# Ruri-Passport-RevA.net
KiCad netlist of a schematic drawn in EasyEDA Pro
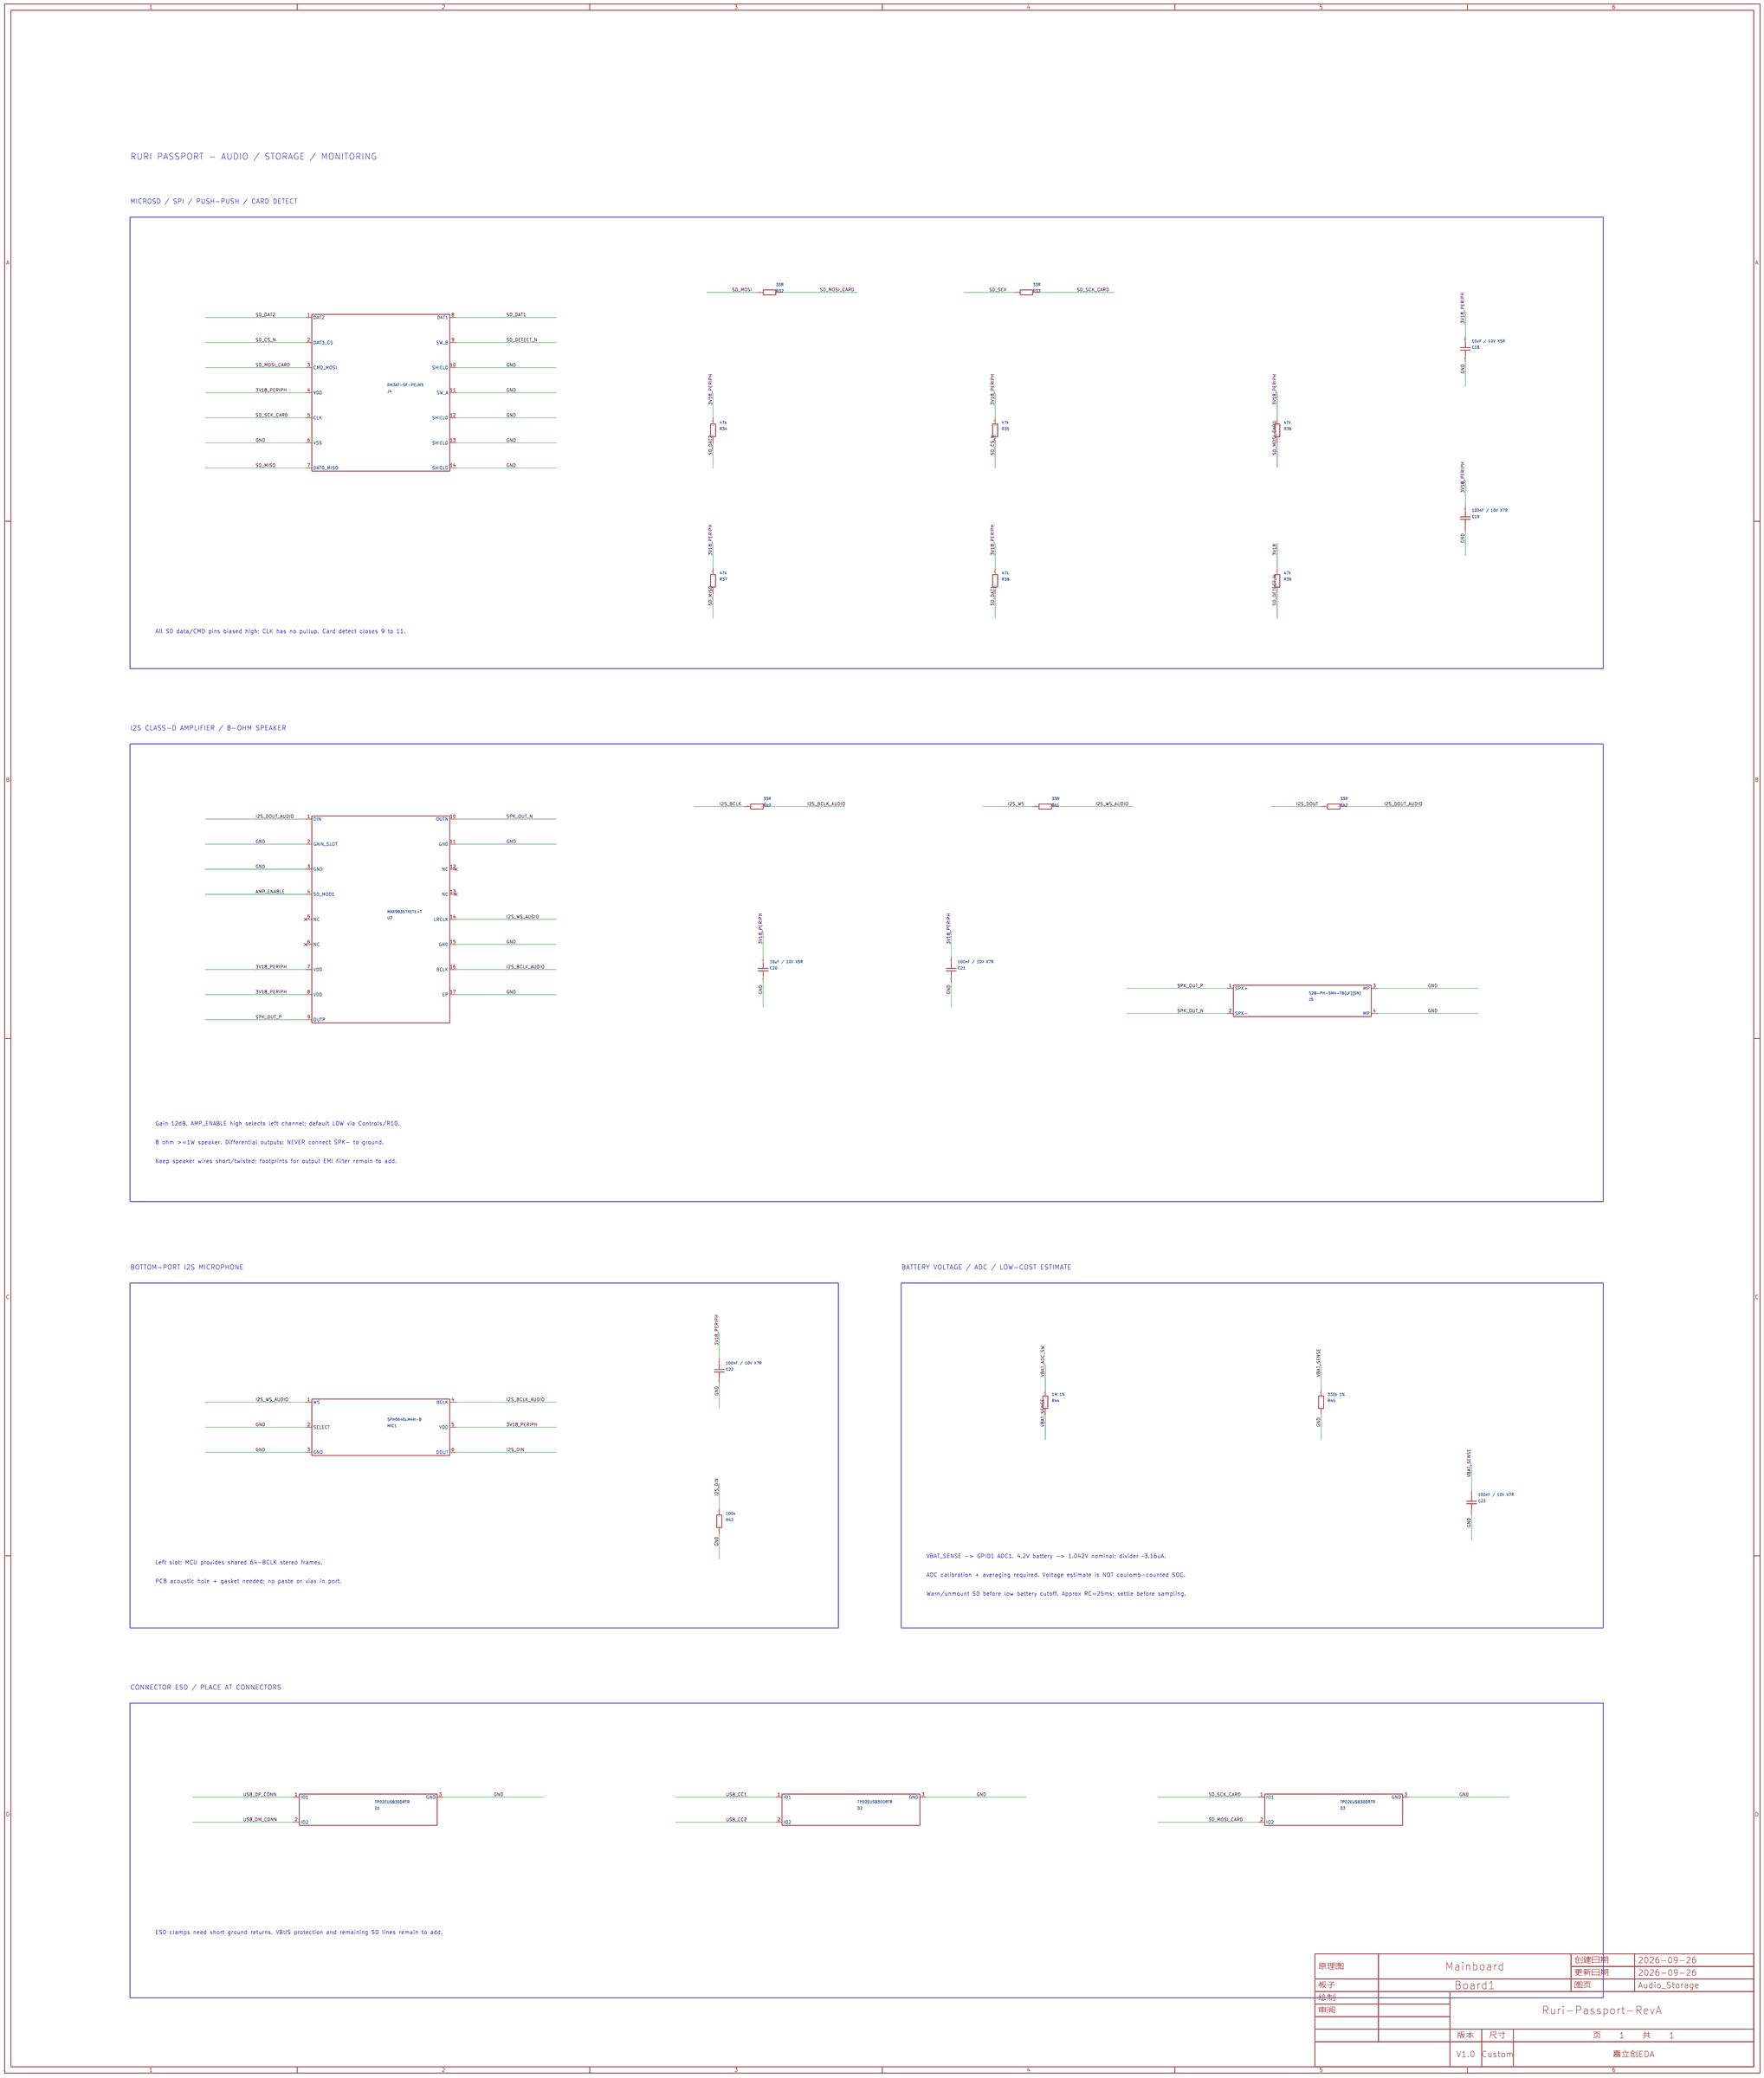
[diagram p0: Audio_Storage]
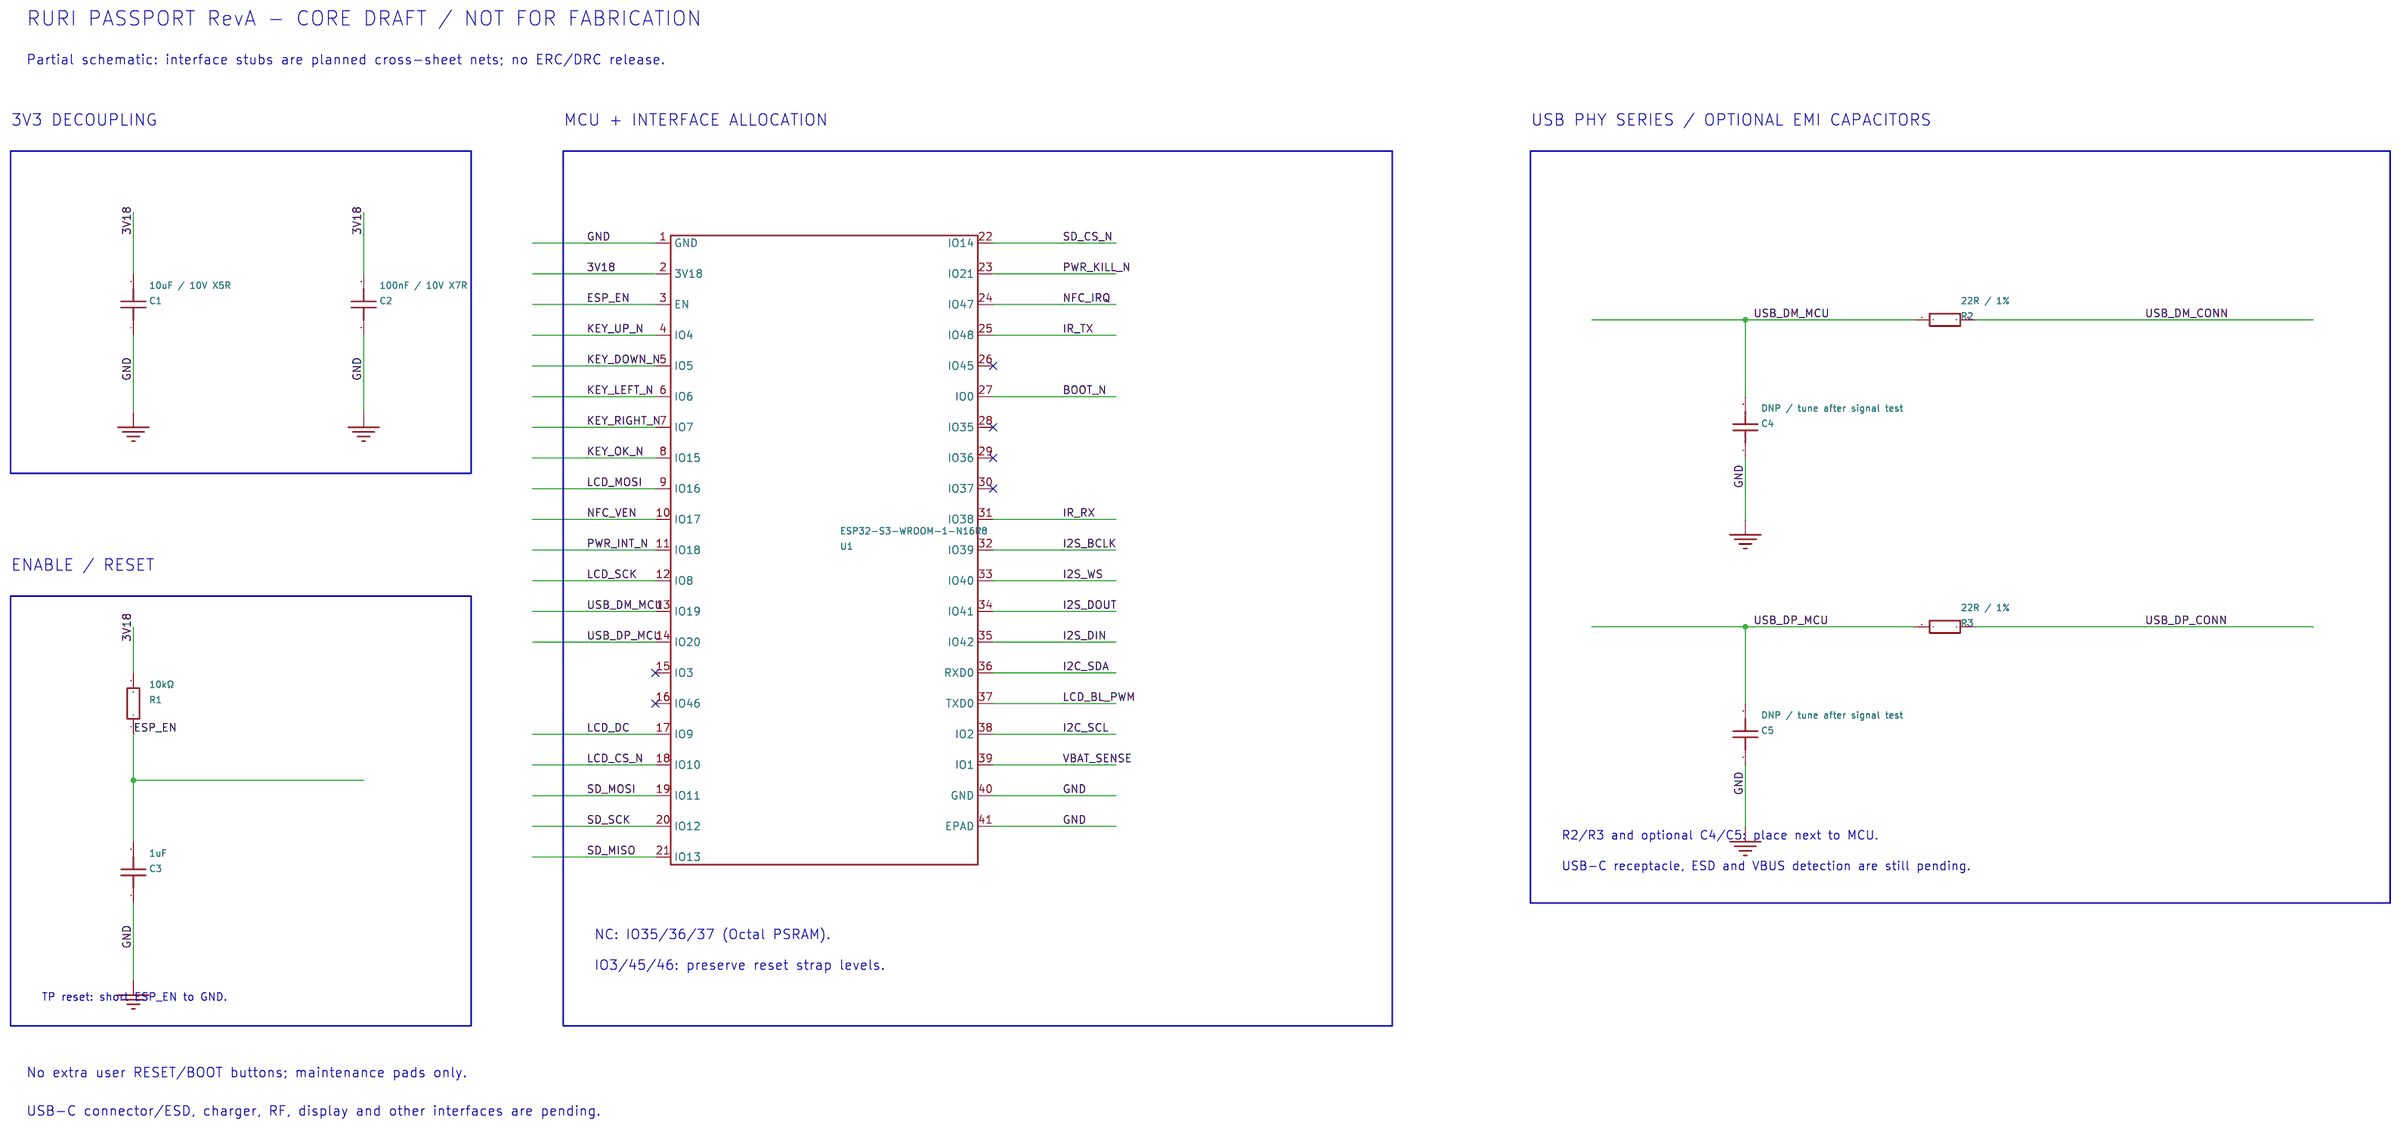
[diagram p1: Core]
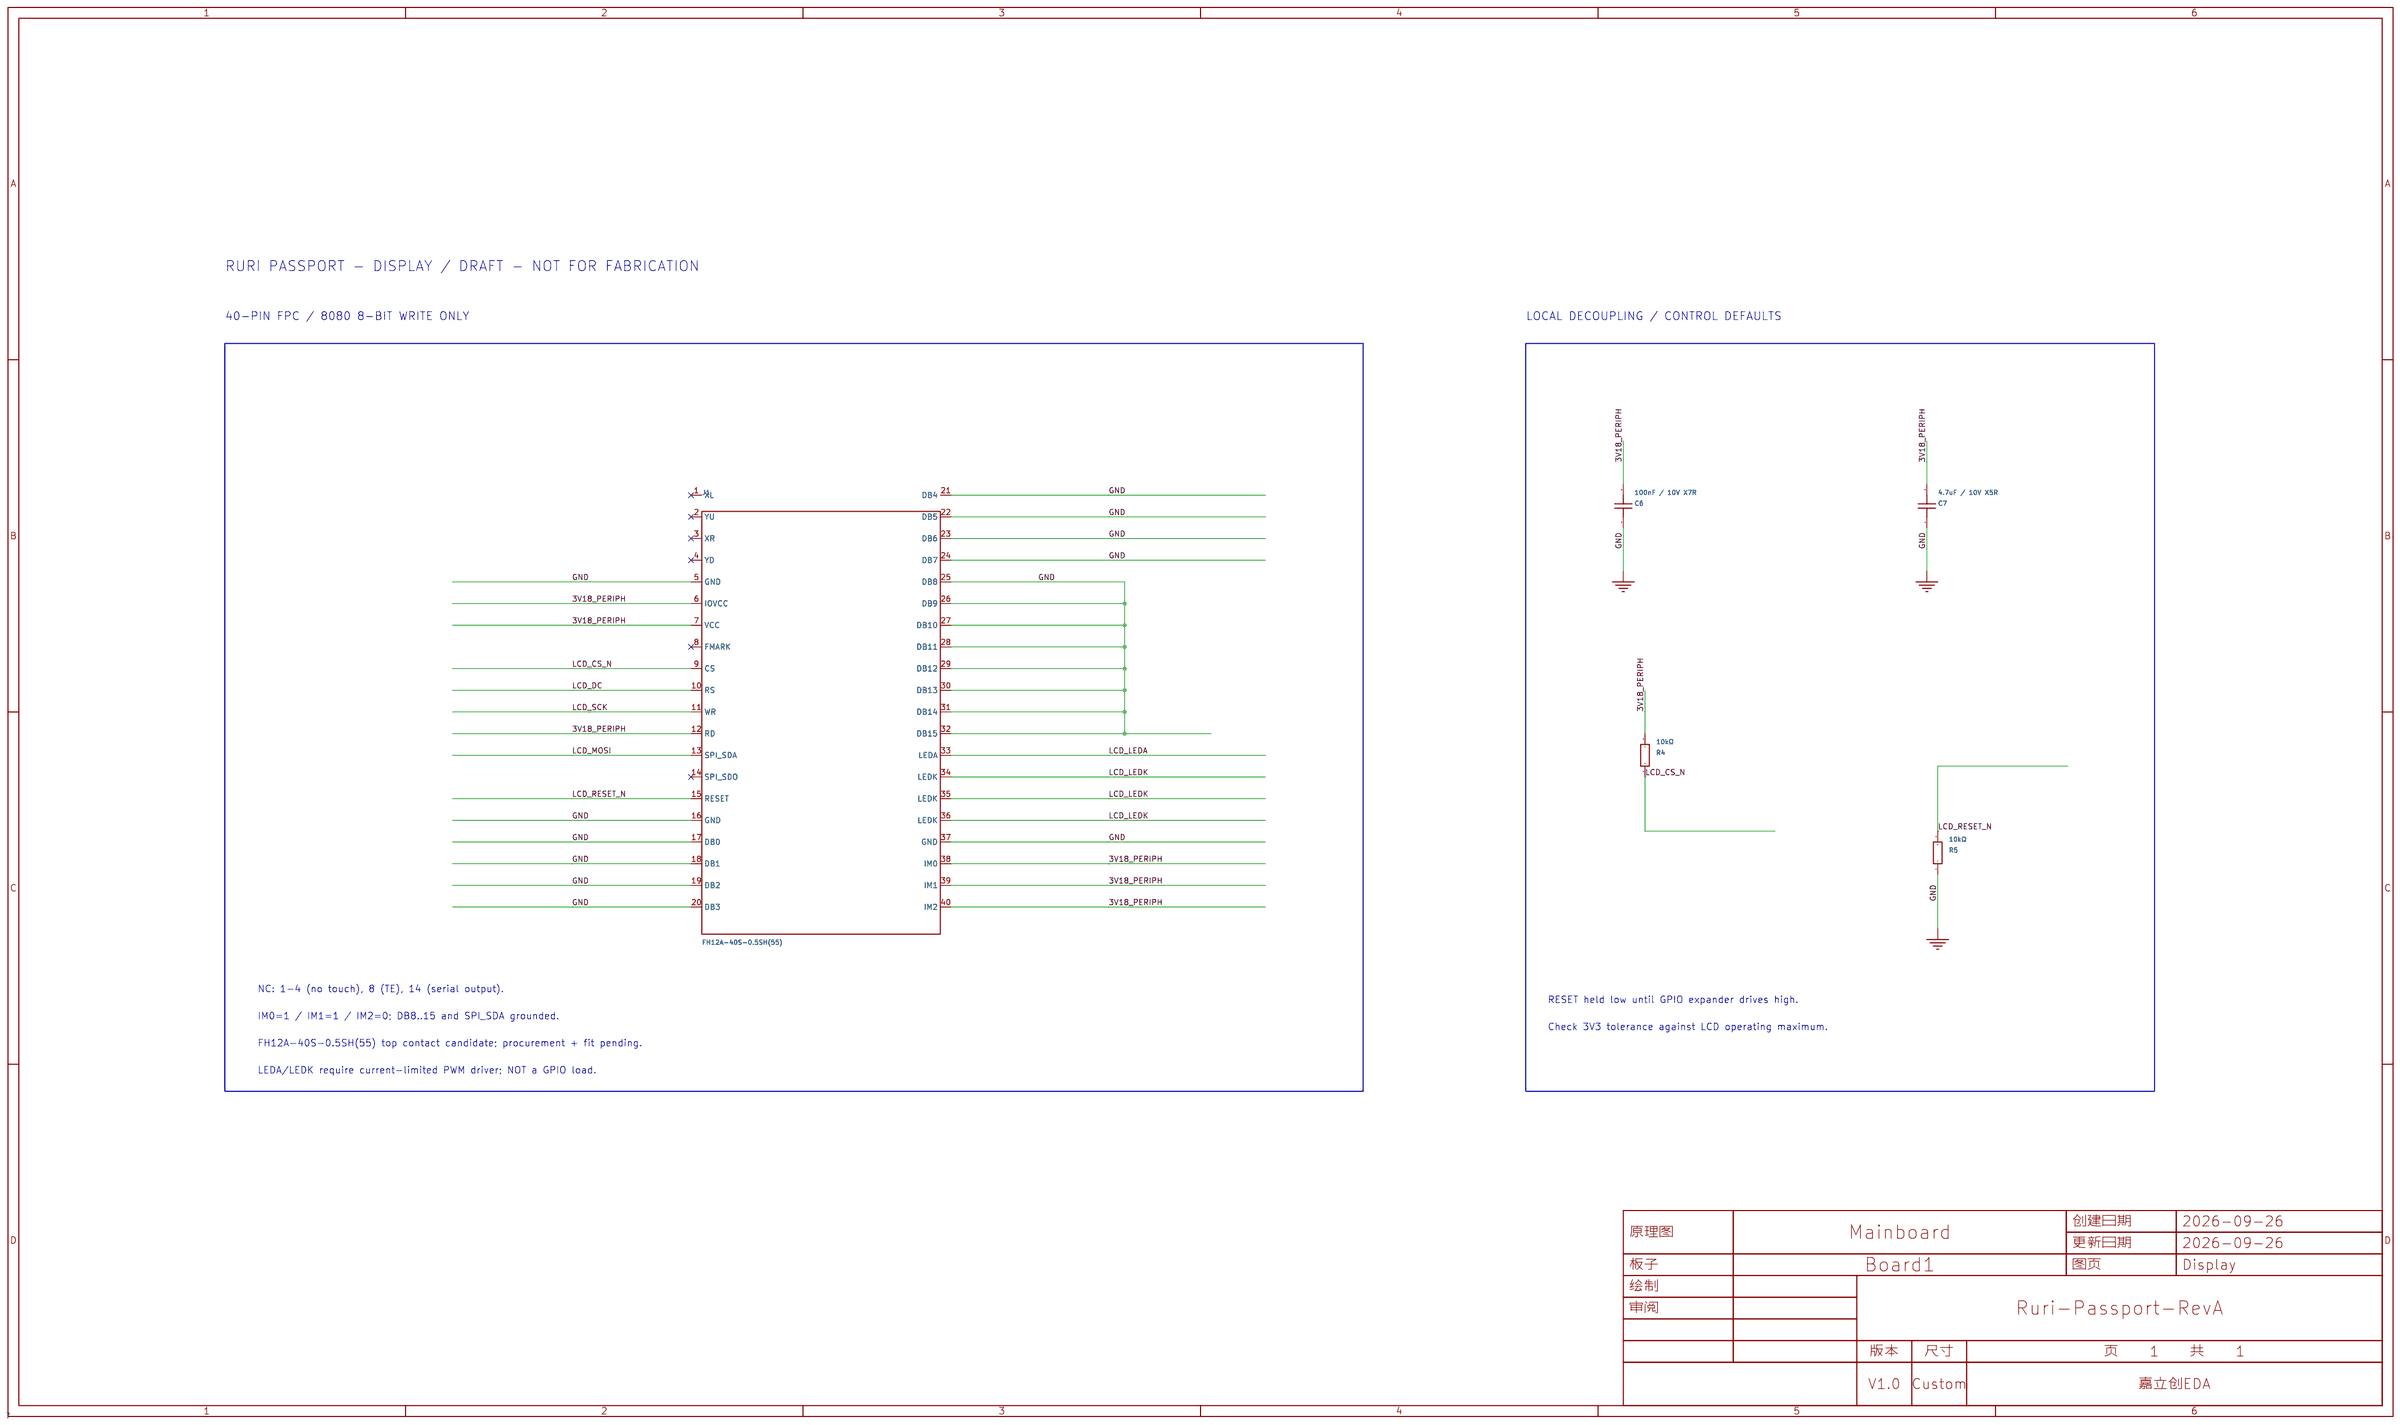
[diagram p2: Display]
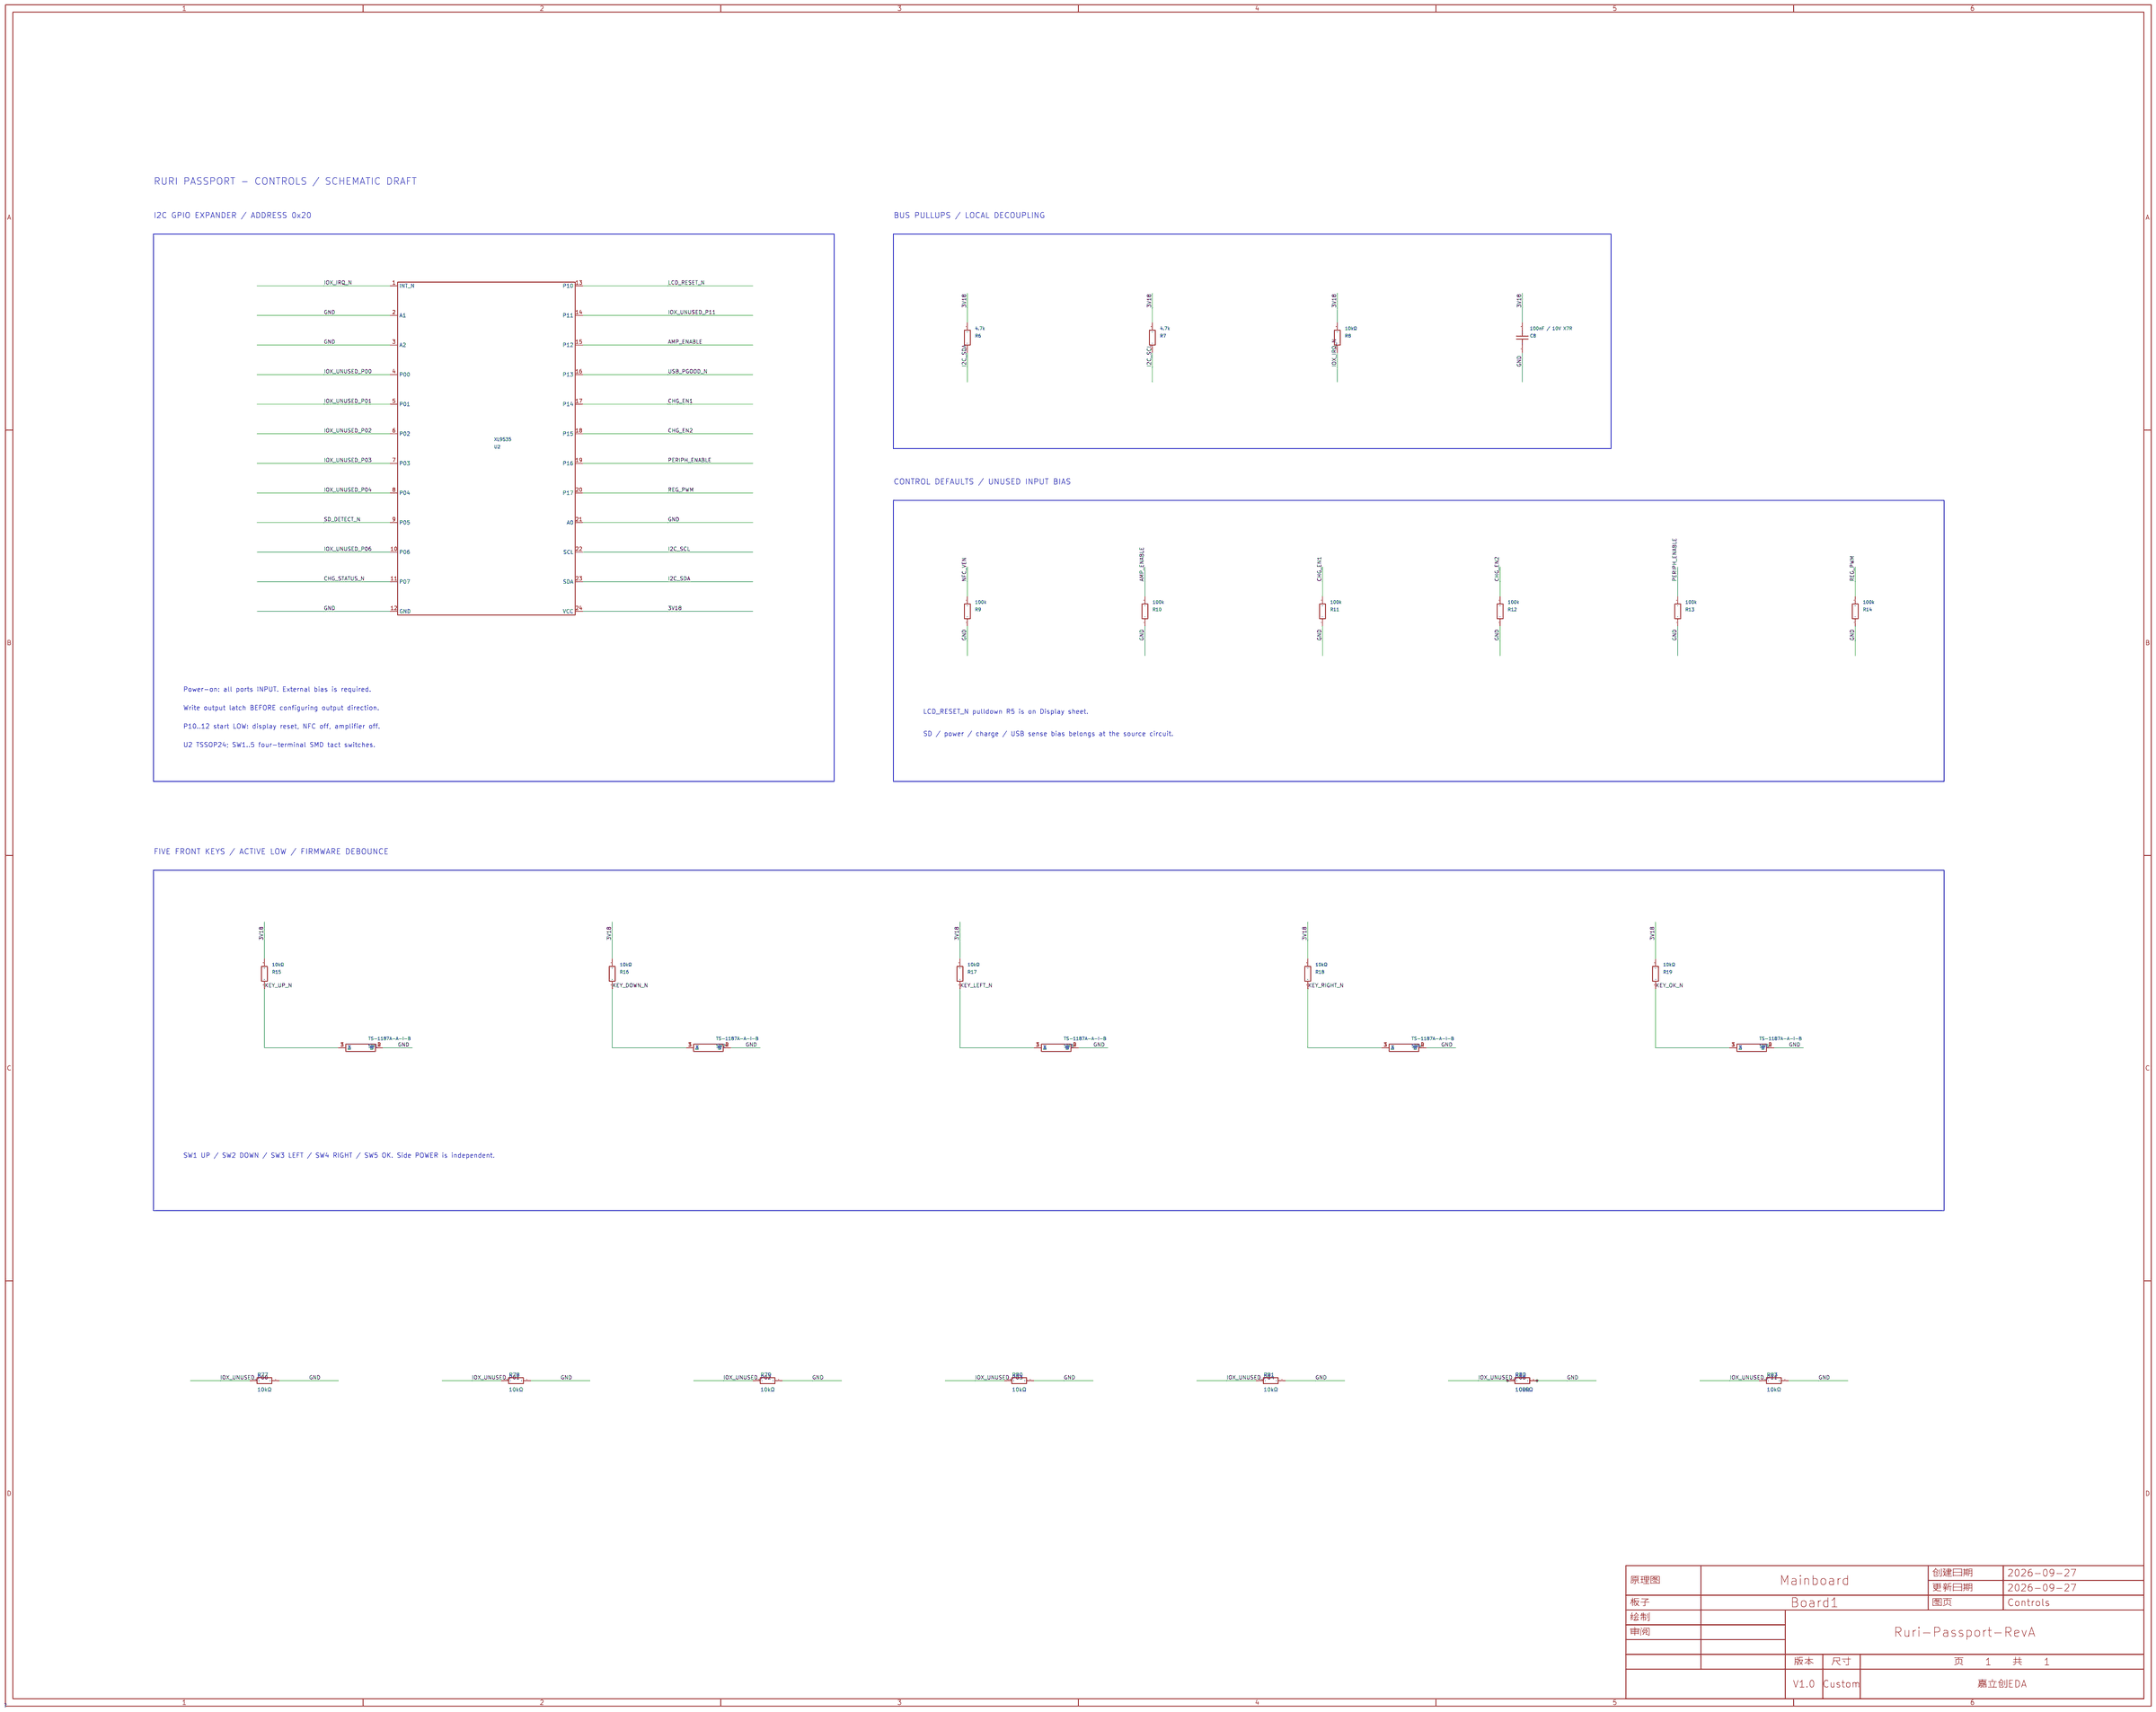
[diagram p3: Controls]
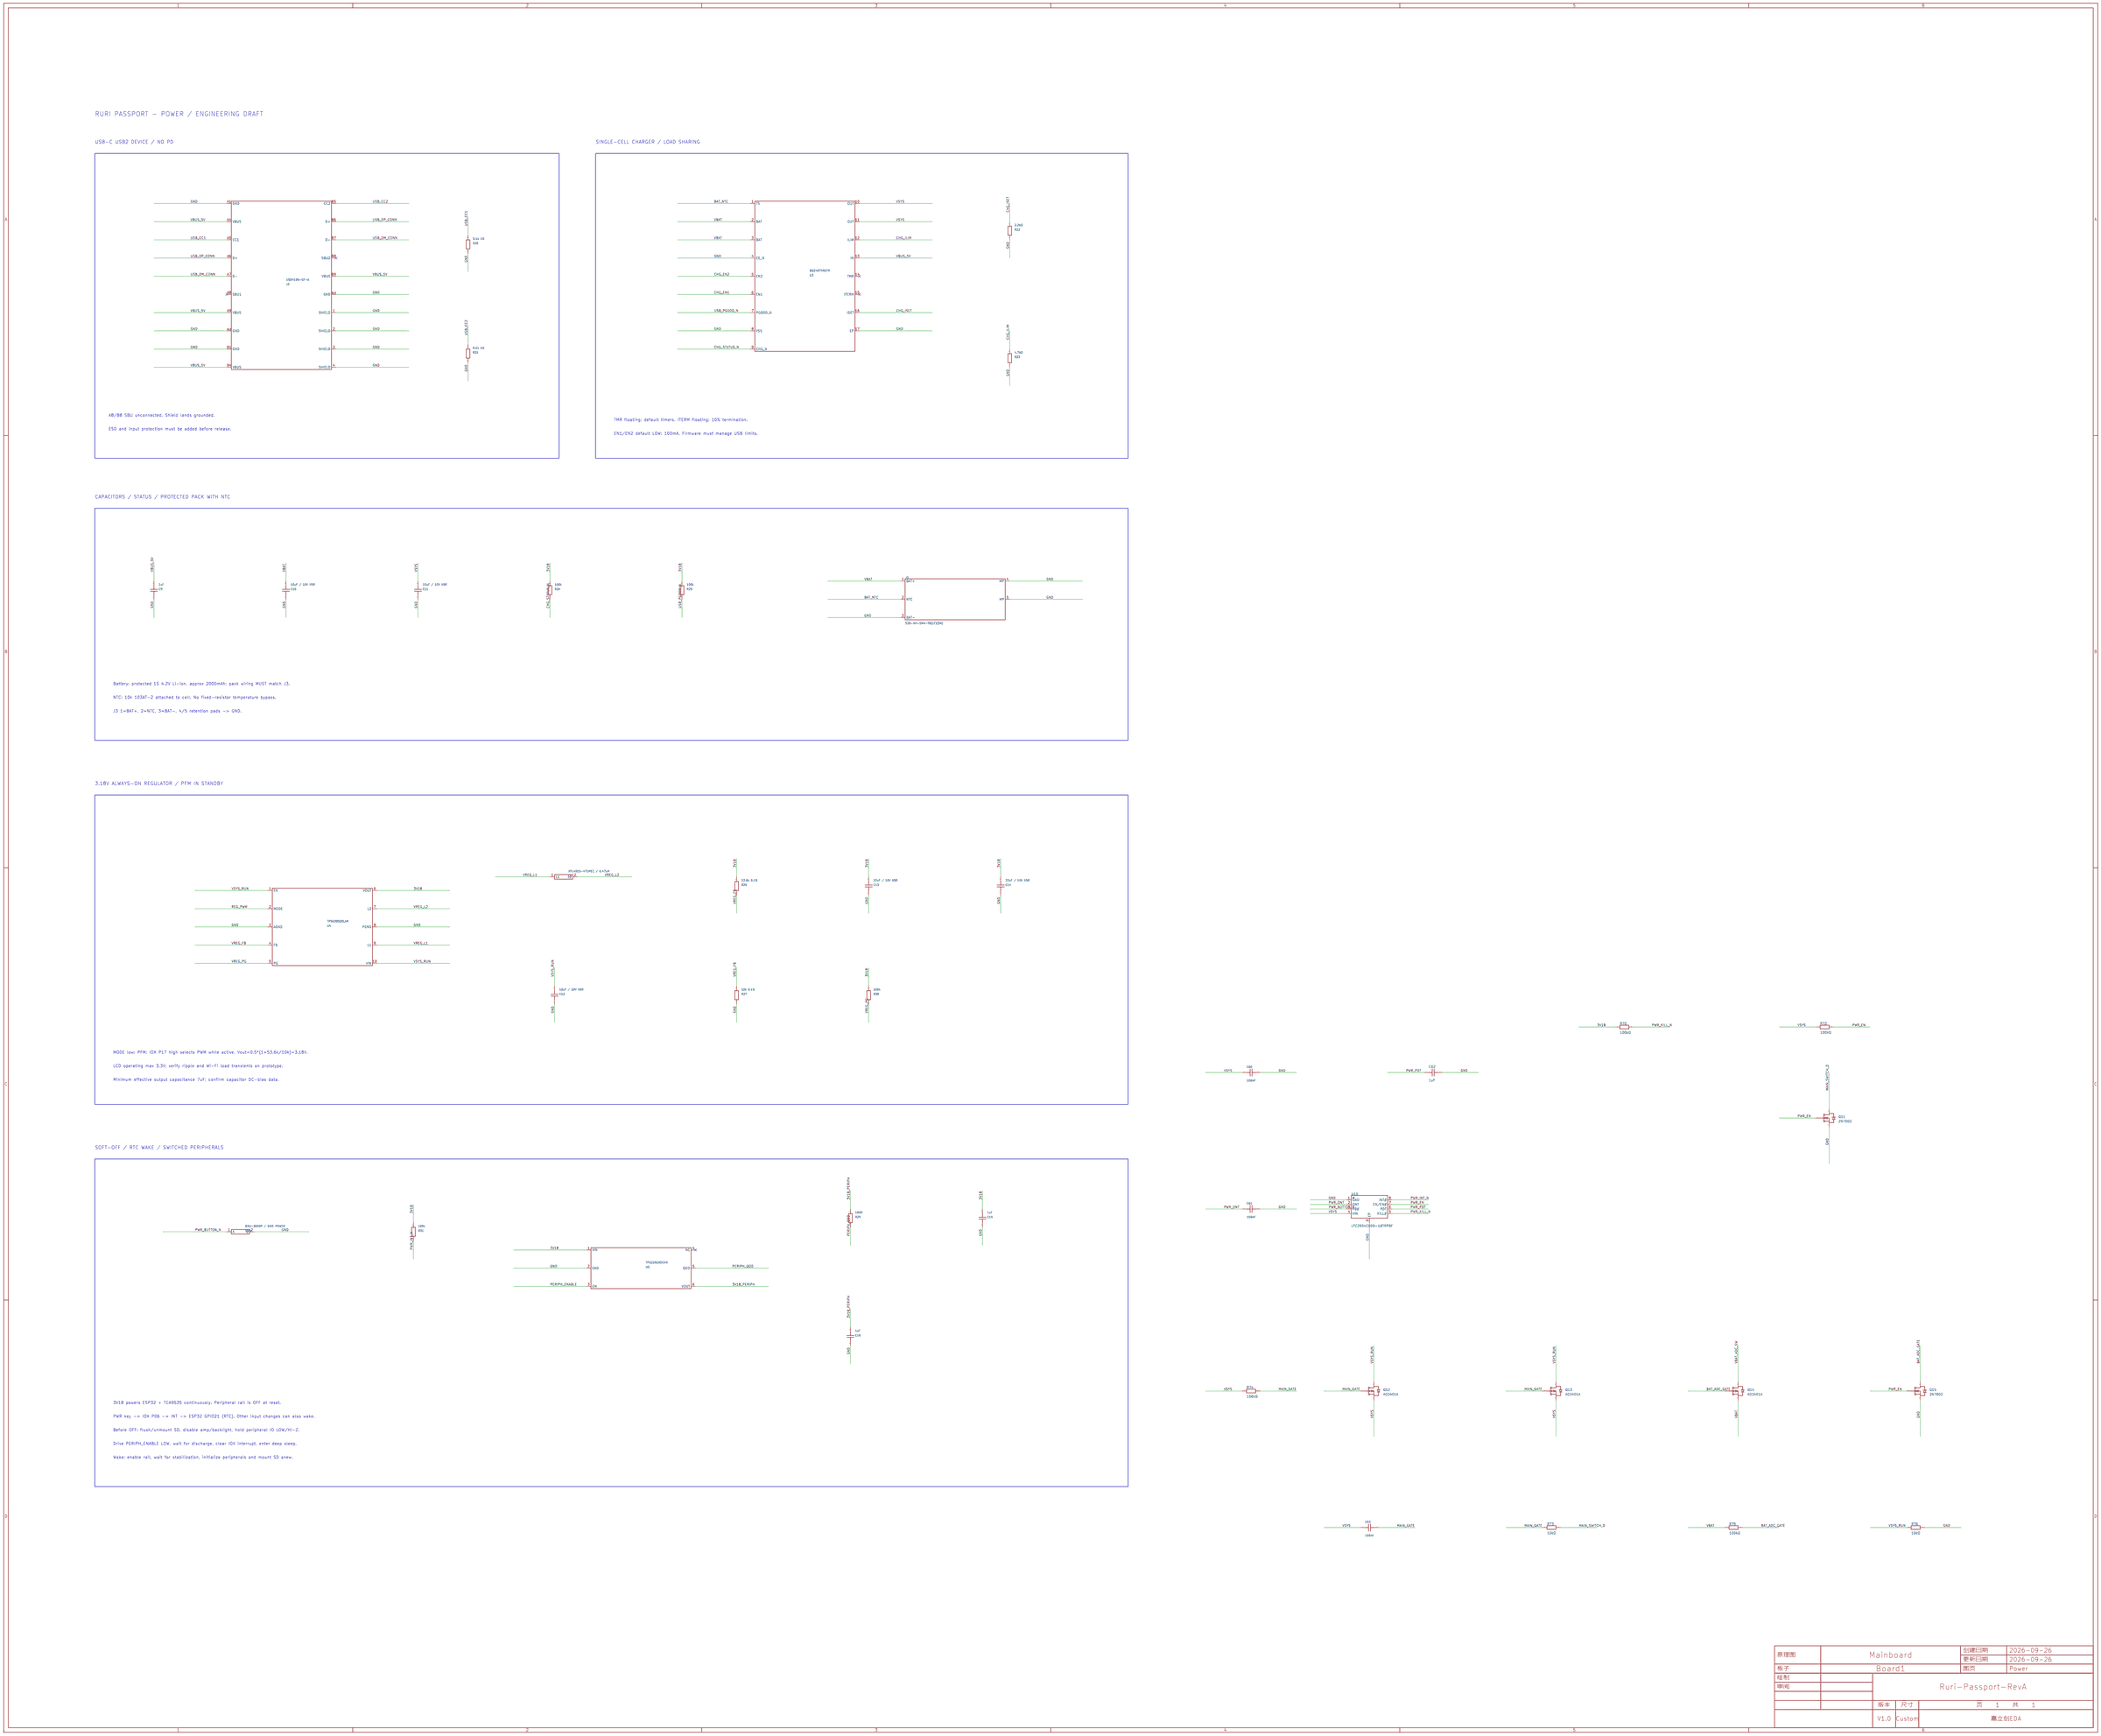
[diagram p4: Power]
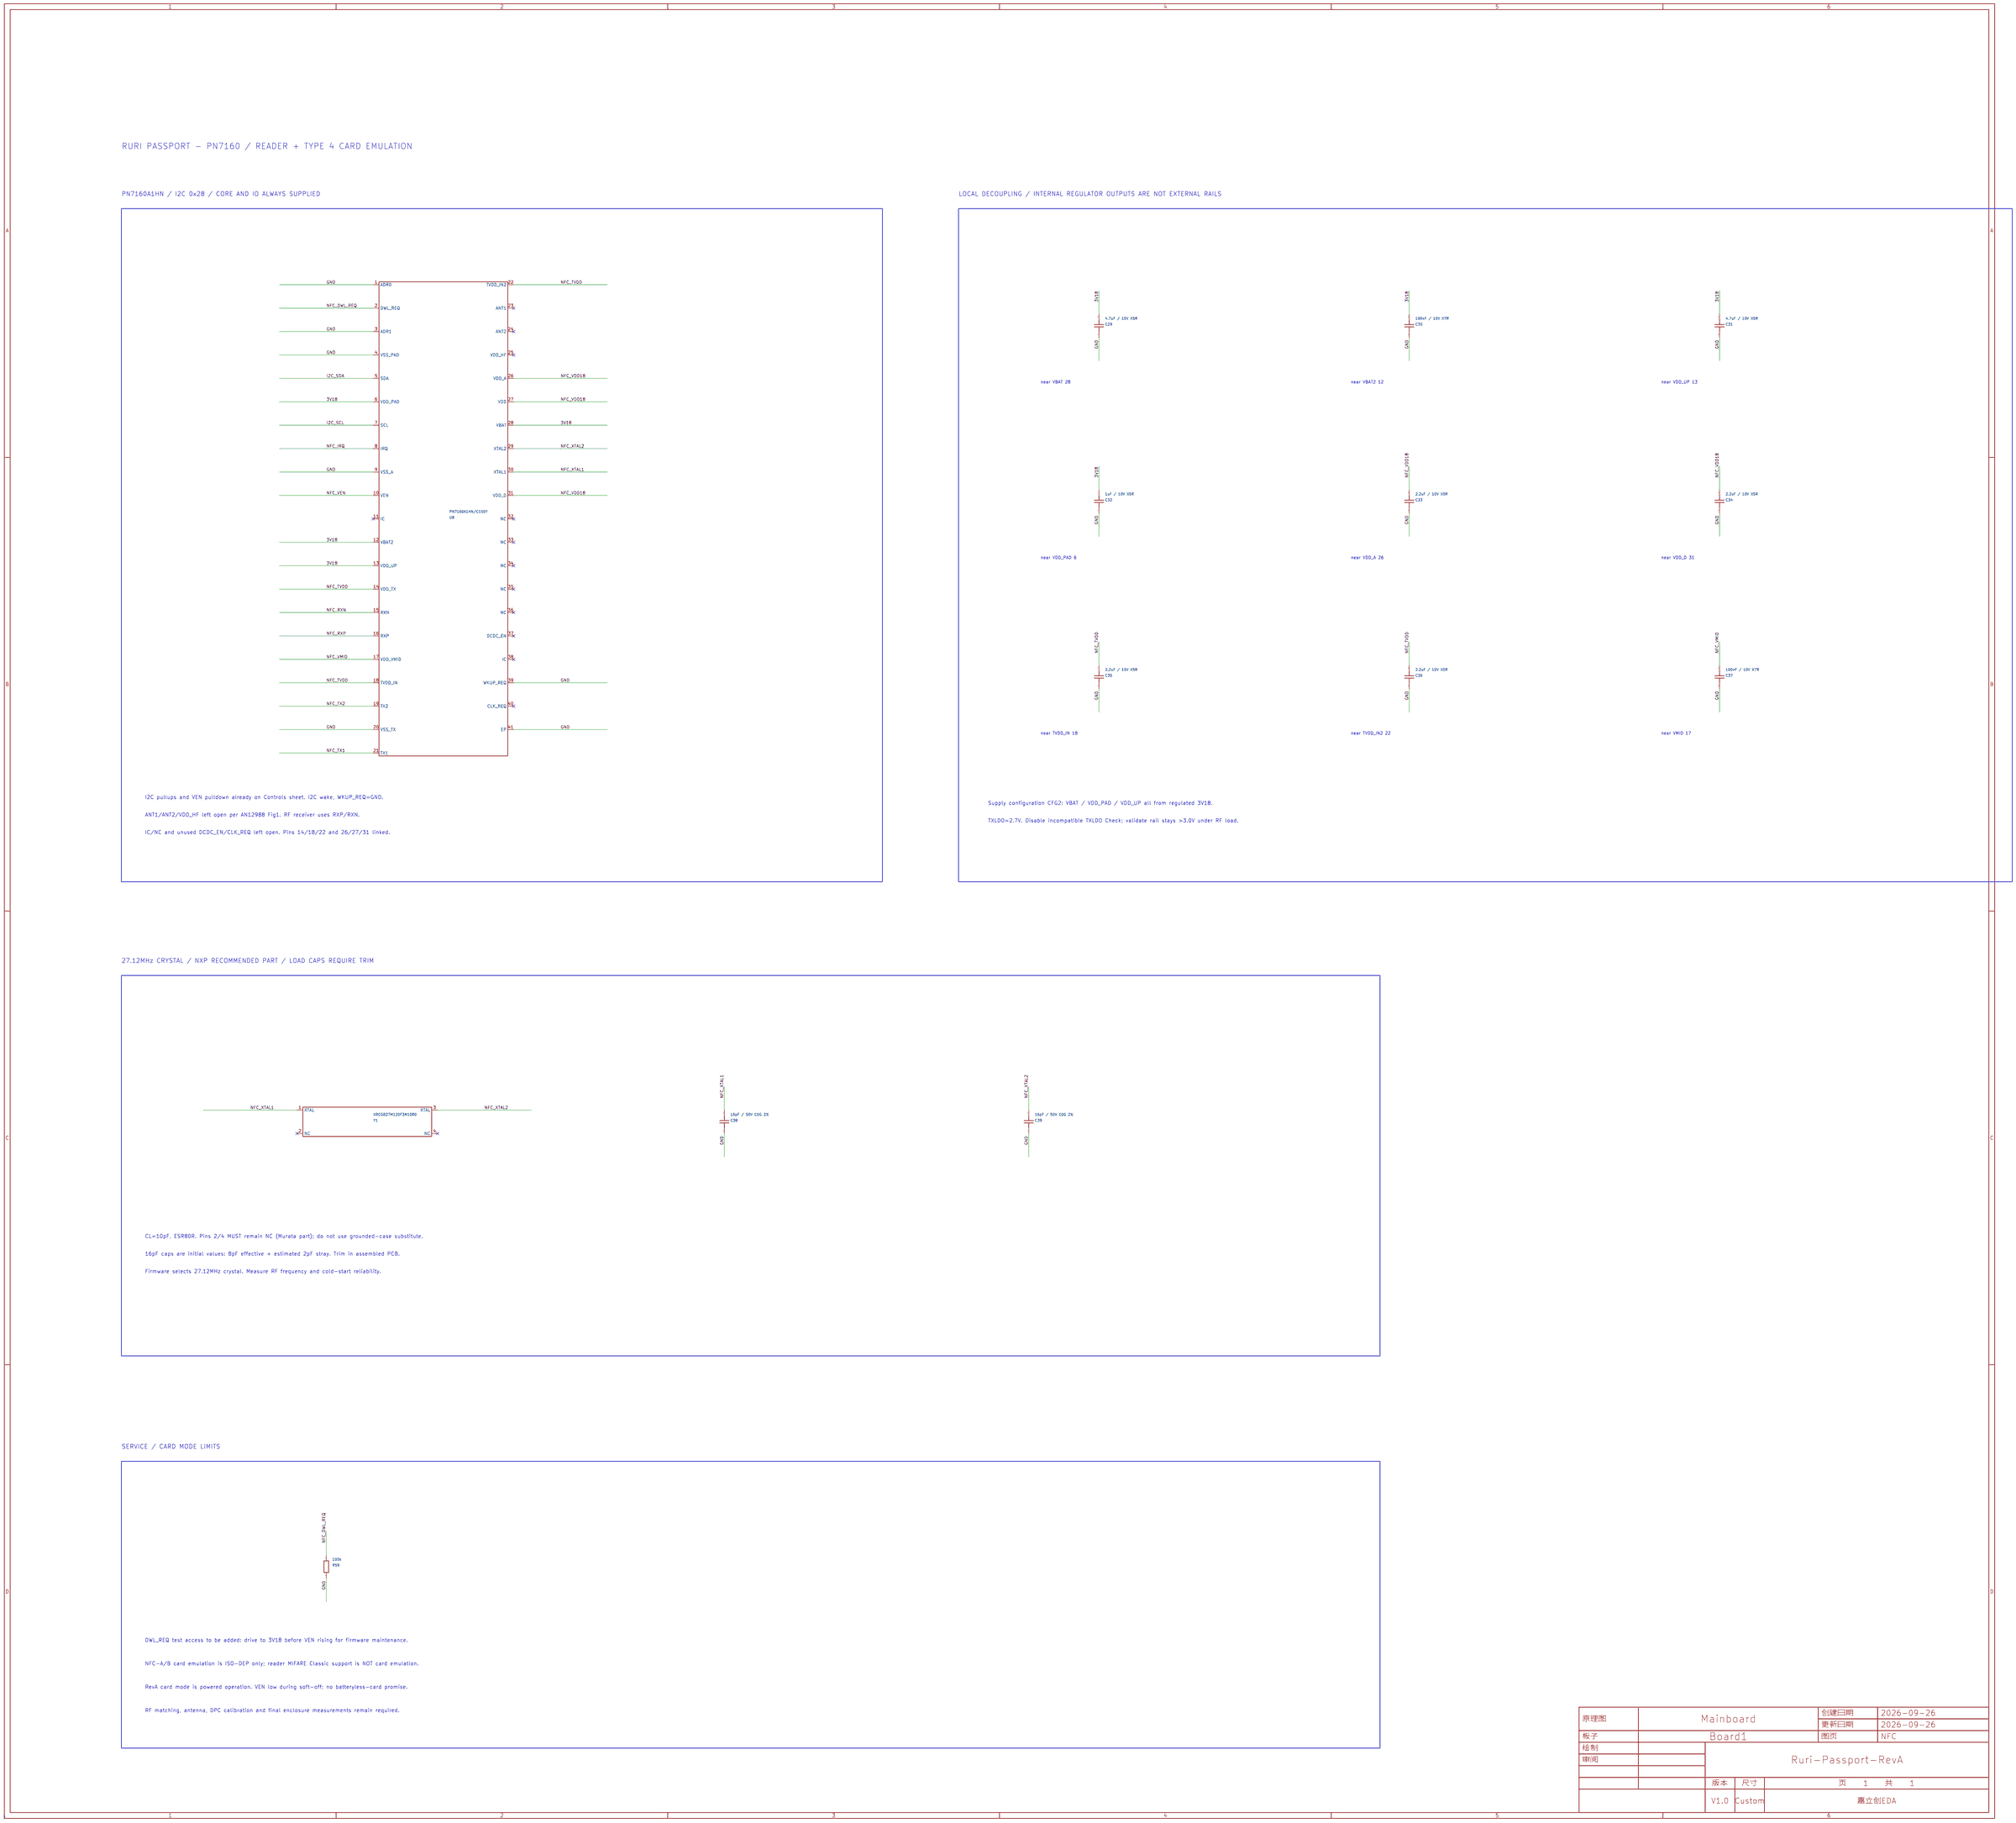
[diagram p5: NFC]
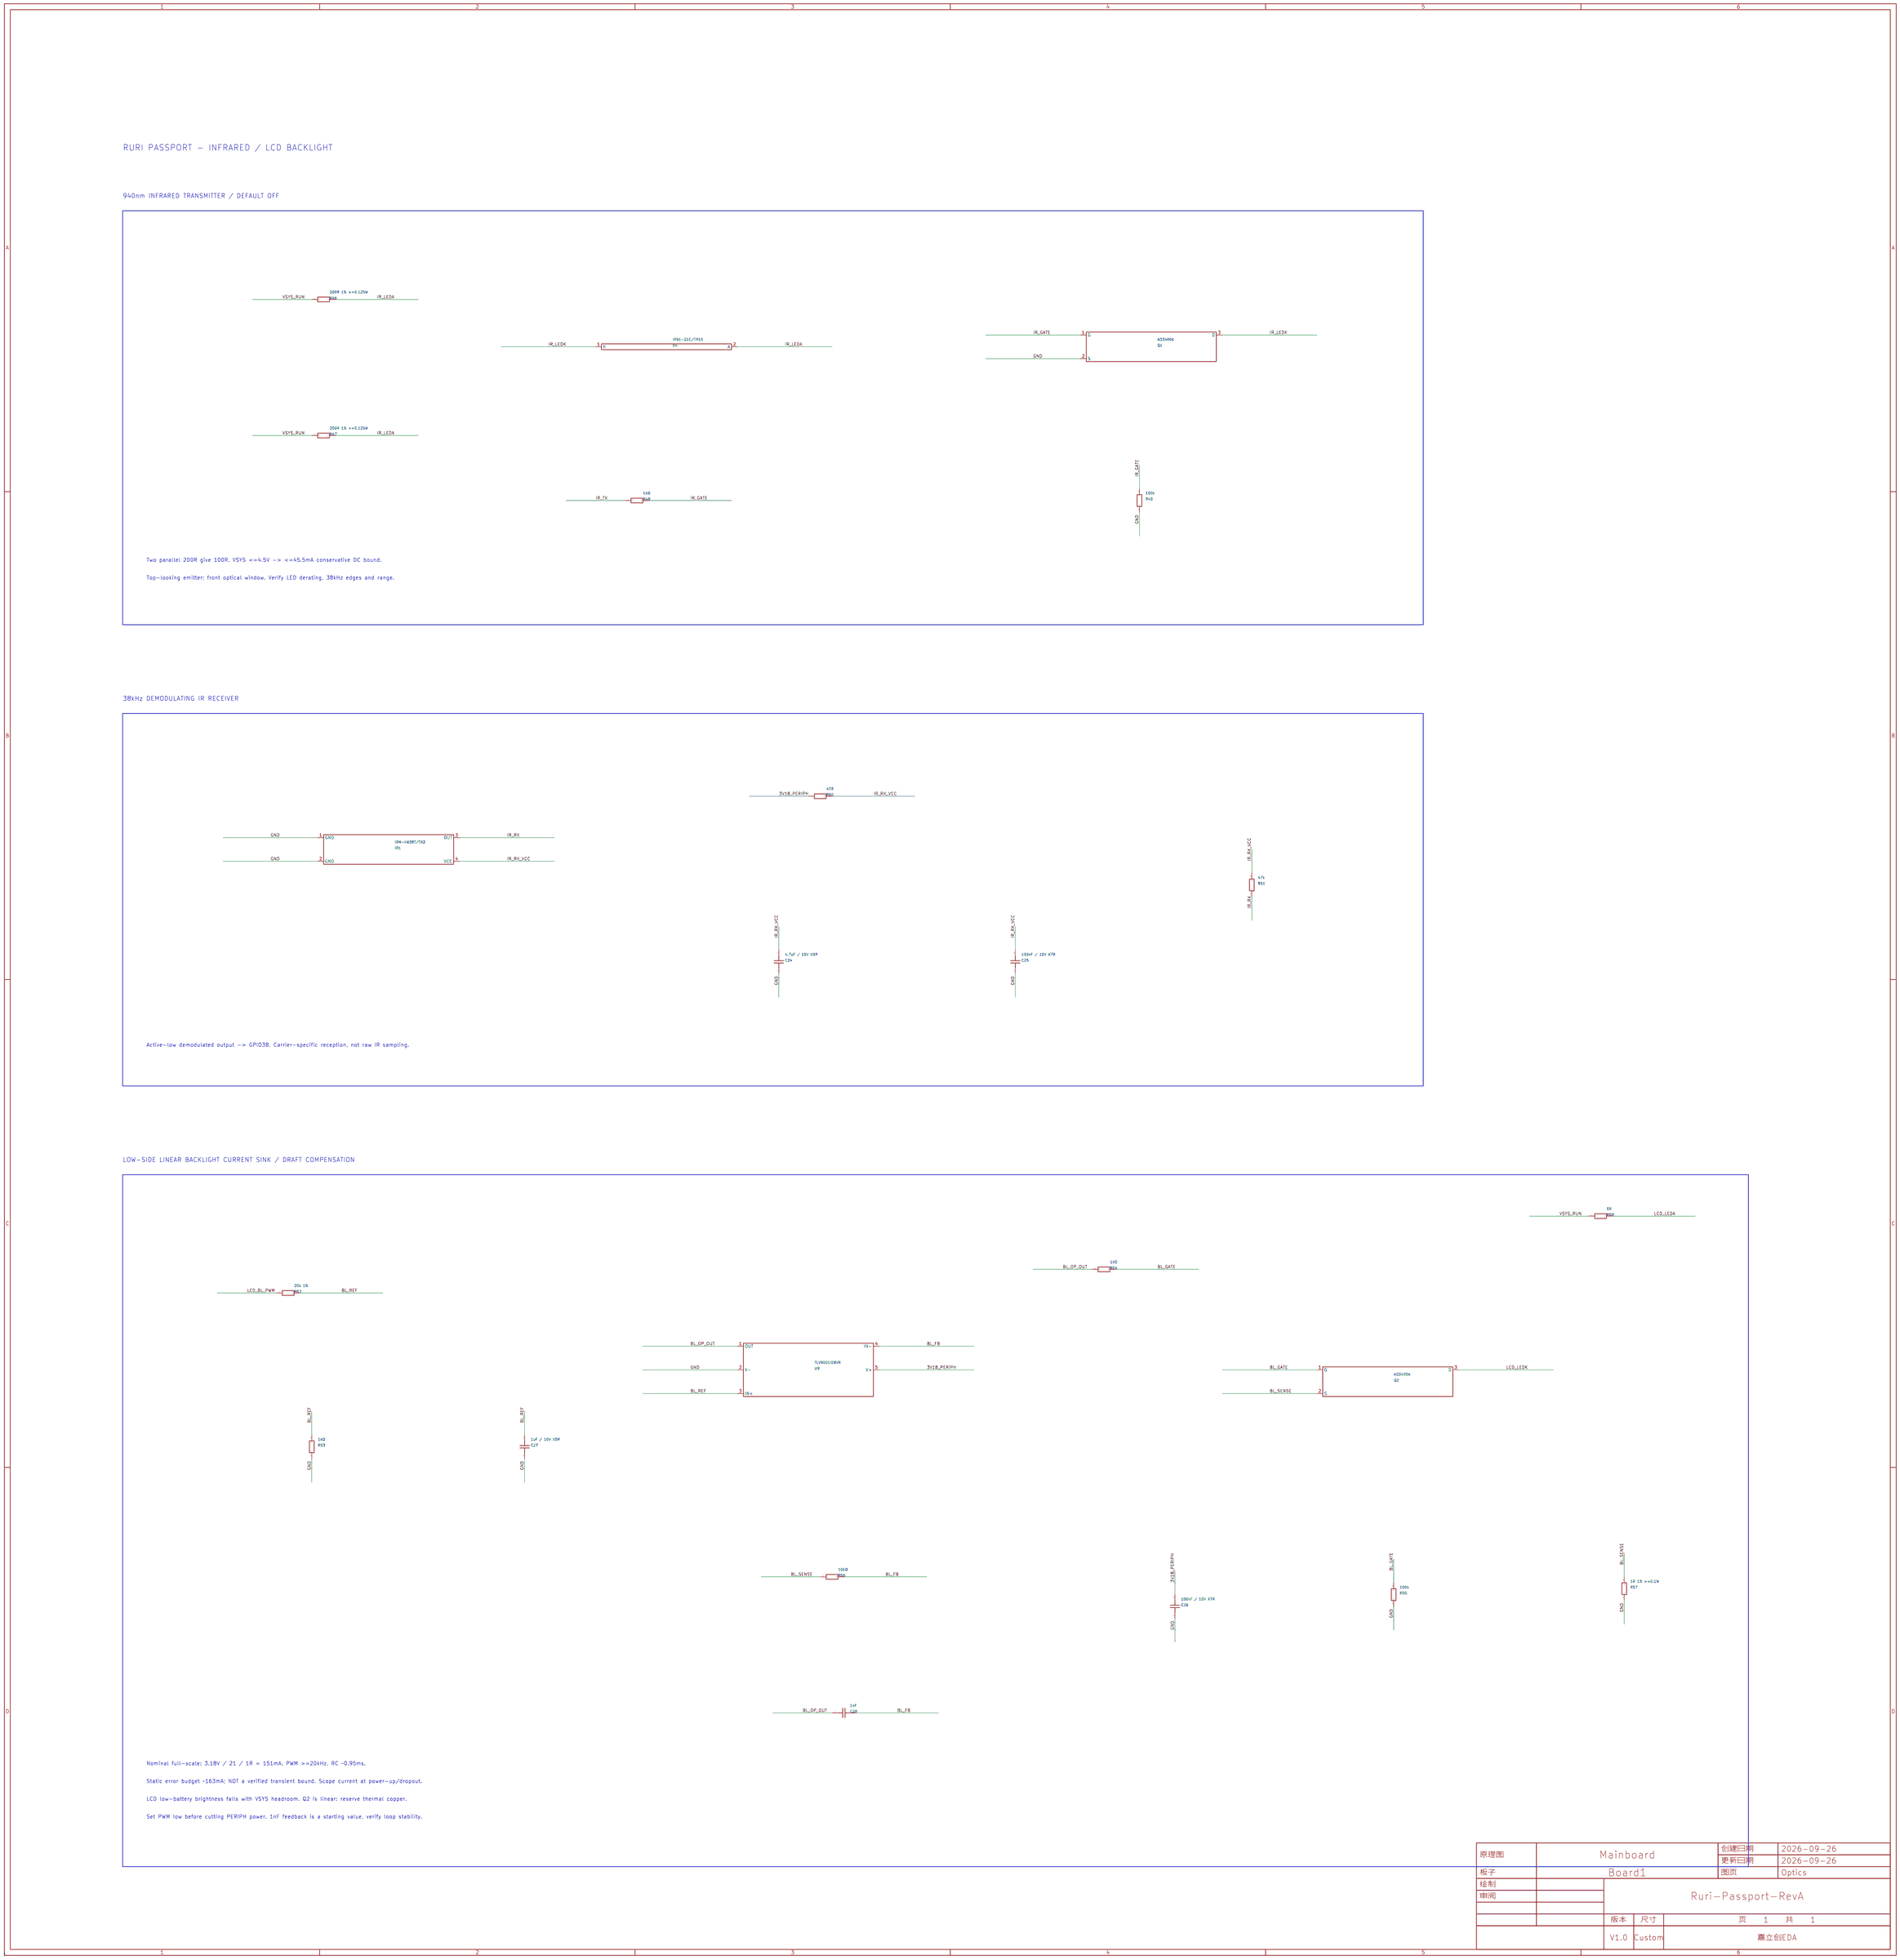
[diagram p6: Optics]
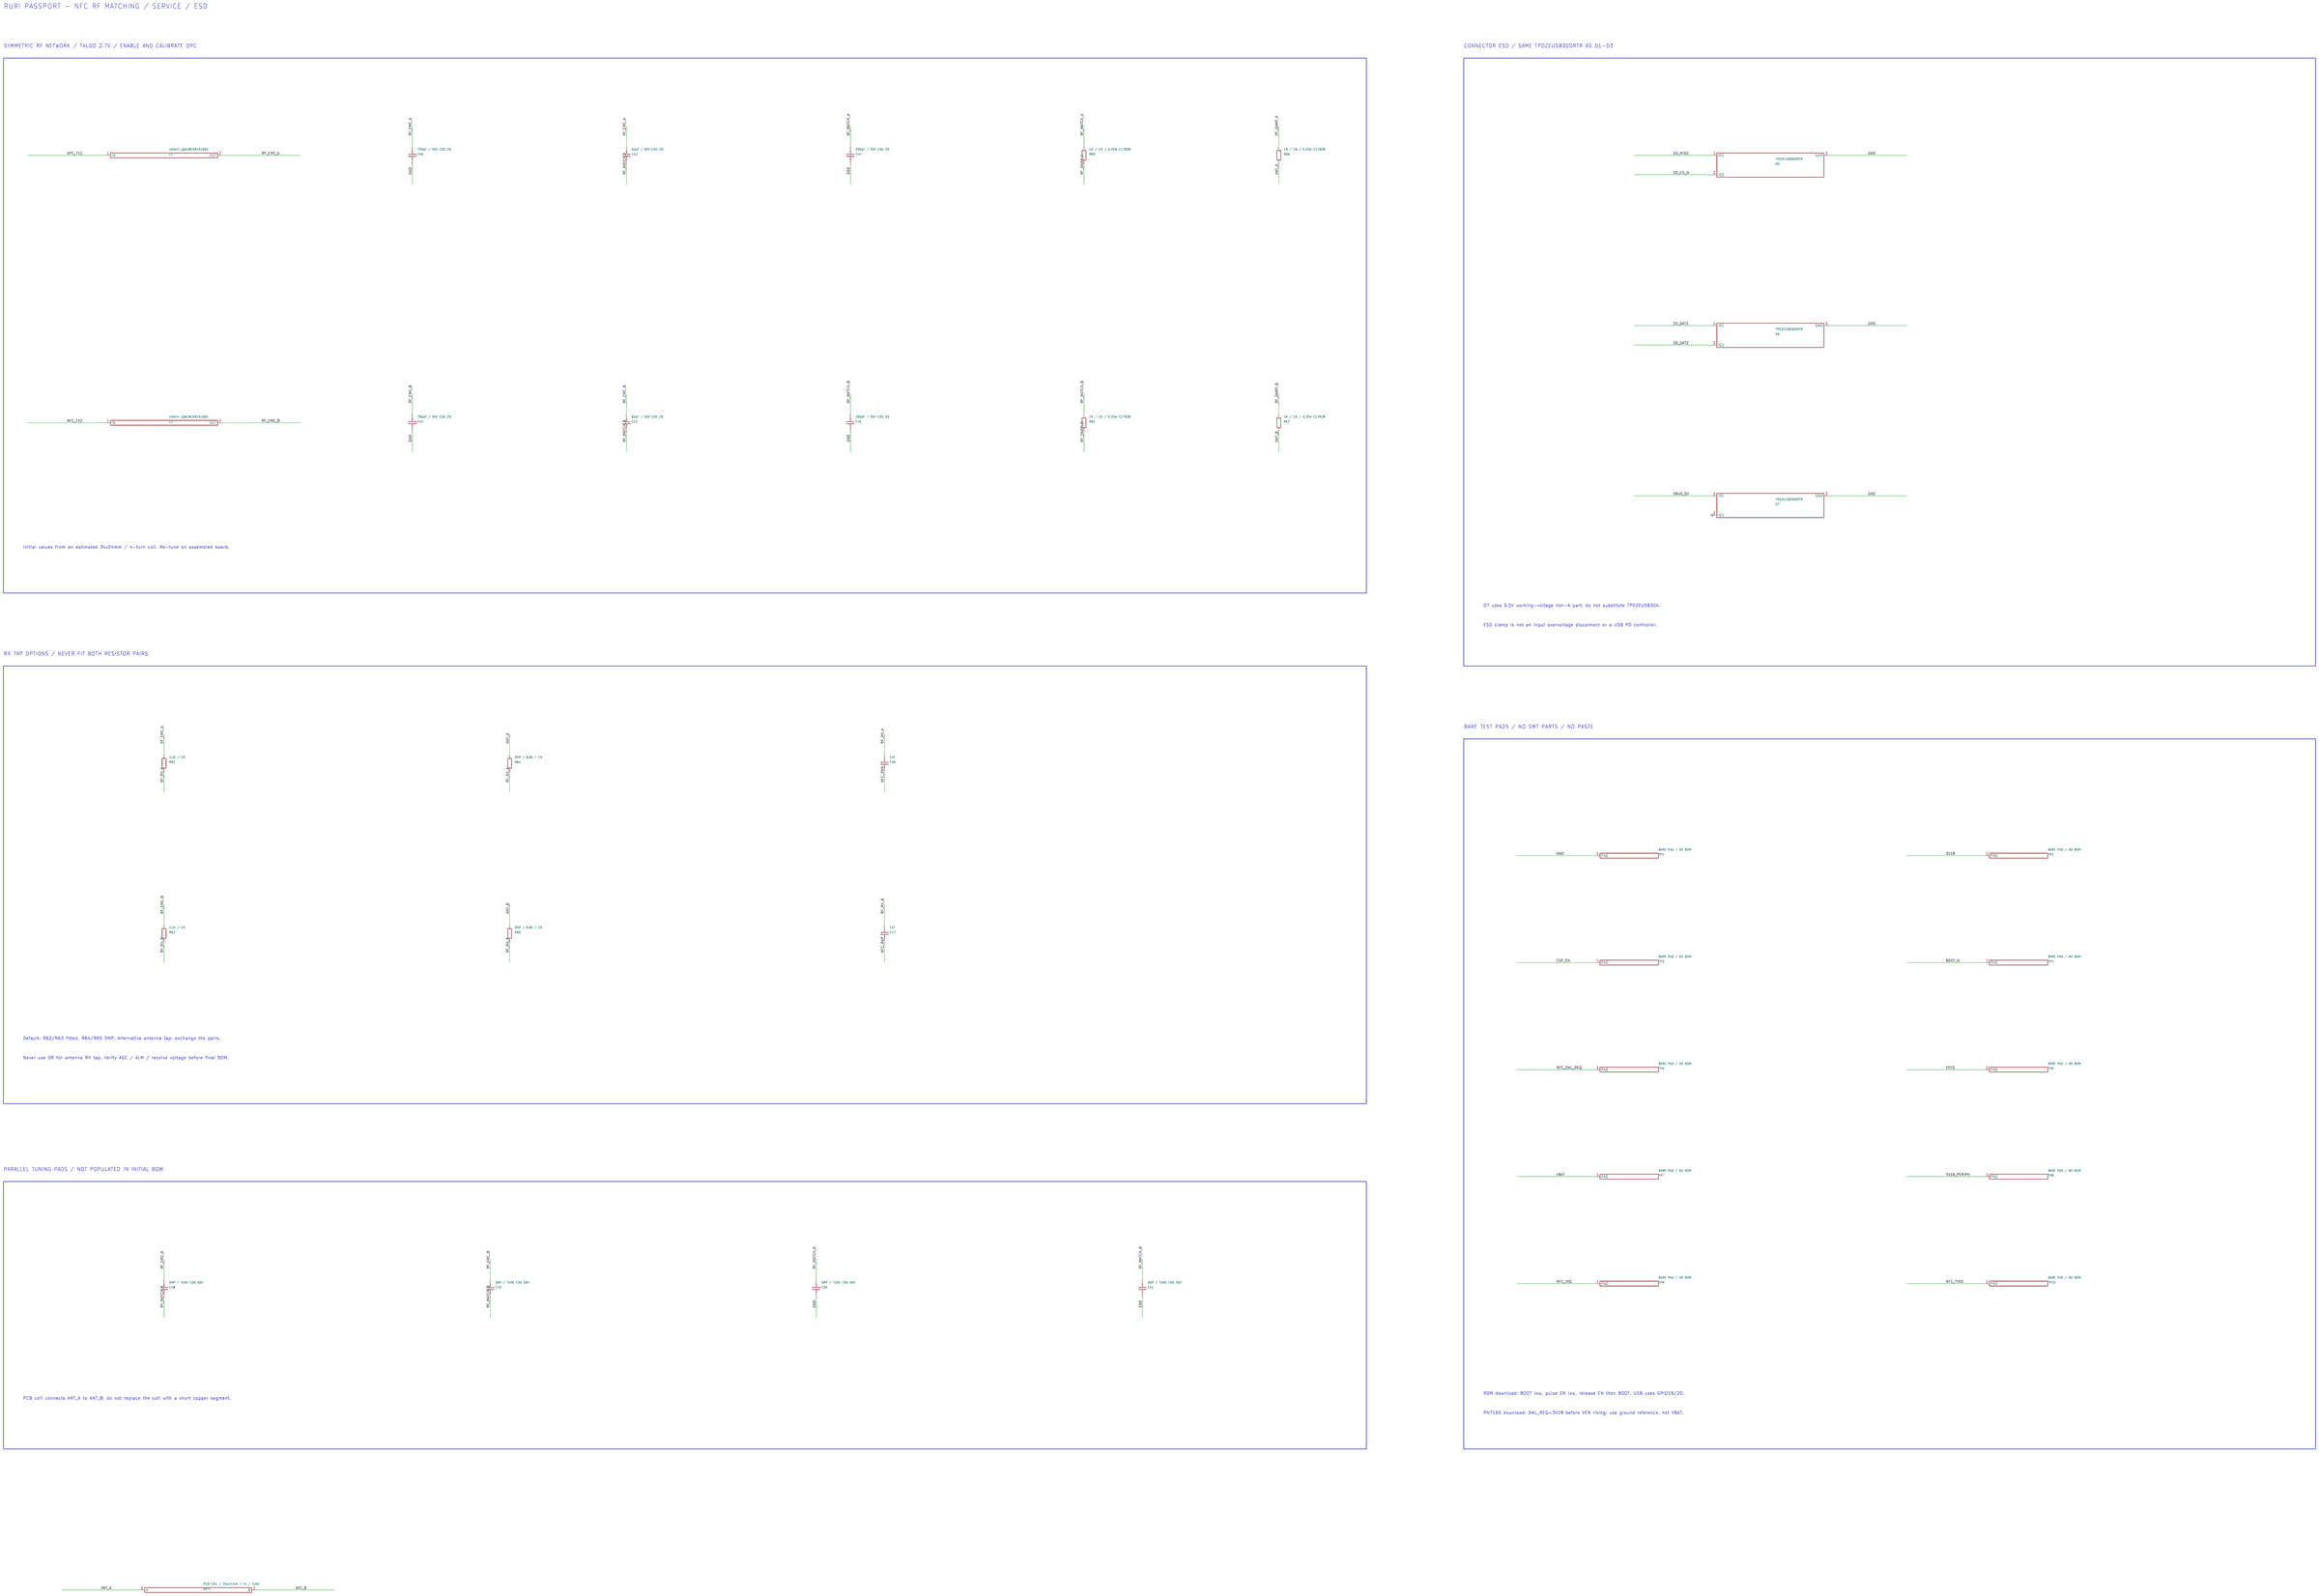
[diagram p7: RF_Service]

(export (version "E")
  (design (tool "Eeschema 10.0.6"))
  (components
    (comp (ref "C18")
      (value "10uF / 10V X5R")
      (footprint "easyedapro:C0603")
      (libsource (lib "easyedapro") (part "CAP"))
    )
    (comp (ref "C19")
      (value "100nF / 10V X7R")
      (footprint "easyedapro:C0603")
      (libsource (lib "easyedapro") (part "CAP"))
    )
    (comp (ref "C20")
      (value "10uF / 10V X5R")
      (footprint "easyedapro:C0603")
      (libsource (lib "easyedapro") (part "CAP"))
    )
    (comp (ref "C21")
      (value "100nF / 10V X7R")
      (footprint "easyedapro:C0603")
      (libsource (lib "easyedapro") (part "CAP"))
    )
    (comp (ref "C22")
      (value "100nF / 10V X7R")
      (footprint "easyedapro:C0603")
      (libsource (lib "easyedapro") (part "CAP"))
    )
    (comp (ref "C23")
      (value "100nF / 10V X7R")
      (footprint "easyedapro:C0603")
      (libsource (lib "easyedapro") (part "CAP"))
    )
    (comp (ref "D1")
      (value "TPD2EUSB30DRTR")
      (footprint "easyedapro:SOT-9X3-3_L1.0-W0.8-P0.35-LS1.0-BR")
      (libsource (lib "easyedapro") (part "RURI_TPD2EUSB30"))
    )
    (comp (ref "D2")
      (value "TPD2EUSB30DRTR")
      (footprint "easyedapro:SOT-9X3-3_L1.0-W0.8-P0.35-LS1.0-BR")
      (libsource (lib "easyedapro") (part "RURI_TPD2EUSB30"))
    )
    (comp (ref "D3")
      (value "TPD2EUSB30DRTR")
      (footprint "easyedapro:SOT-9X3-3_L1.0-W0.8-P0.35-LS1.0-BR")
      (libsource (lib "easyedapro") (part "RURI_TPD2EUSB30"))
    )
    (comp (ref "J4")
      (value "DM3AT-SF-PEJM5")
      (footprint "easyedapro:SD-SMD_DM3AT-SF-PEJM5")
      (libsource (lib "easyedapro") (part "RURI_DM3AT"))
    )
    (comp (ref "J5")
      (value "S2B-PH-SM4-TB(LF)(SN)")
      (footprint "easyedapro:CONN-SMD_P2.00_S2B-PH-SM4-TB-LF-SN")
      (libsource (lib "easyedapro") (part "RURI_SPEAKER_PH2"))
    )
    (comp (ref "MIC1")
      (value "SPH0645LM4H-B")
      (footprint "easyedapro:MIC-SMD_6P-L3.5-W2.7-P0.90-BL")
      (libsource (lib "easyedapro") (part "RURI_SPH0645"))
    )
    (comp (ref "R32")
      (value "33R")
      (footprint "easyedapro:R0603")
      (fields
        (field (name "Manufacturer Part") "0603WAF1001T5E")
        (field (name "Manufacturer") "UNI-ROYAL(厚声)")
      )
      (libsource (lib "easyedapro") (part "RES"))
    )
    (comp (ref "R33")
      (value "33R")
      (footprint "easyedapro:R0603")
      (fields
        (field (name "Manufacturer Part") "0603WAF1001T5E")
        (field (name "Manufacturer") "UNI-ROYAL(厚声)")
      )
      (libsource (lib "easyedapro") (part "RES"))
    )
    (comp (ref "R34")
      (value "47k")
      (footprint "easyedapro:R0603")
      (fields
        (field (name "Manufacturer Part") "0603WAF1001T5E")
        (field (name "Manufacturer") "UNI-ROYAL(厚声)")
      )
      (libsource (lib "easyedapro") (part "RES"))
    )
    (comp (ref "R35")
      (value "47k")
      (footprint "easyedapro:R0603")
      (fields
        (field (name "Manufacturer Part") "0603WAF1001T5E")
        (field (name "Manufacturer") "UNI-ROYAL(厚声)")
      )
      (libsource (lib "easyedapro") (part "RES"))
    )
    (comp (ref "R36")
      (value "47k")
      (footprint "easyedapro:R0603")
      (fields
        (field (name "Manufacturer Part") "0603WAF1001T5E")
        (field (name "Manufacturer") "UNI-ROYAL(厚声)")
      )
      (libsource (lib "easyedapro") (part "RES"))
    )
    (comp (ref "R37")
      (value "47k")
      (footprint "easyedapro:R0603")
      (fields
        (field (name "Manufacturer Part") "0603WAF1001T5E")
        (field (name "Manufacturer") "UNI-ROYAL(厚声)")
      )
      (libsource (lib "easyedapro") (part "RES"))
    )
    (comp (ref "R38")
      (value "47k")
      (footprint "easyedapro:R0603")
      (fields
        (field (name "Manufacturer Part") "0603WAF1001T5E")
        (field (name "Manufacturer") "UNI-ROYAL(厚声)")
      )
      (libsource (lib "easyedapro") (part "RES"))
    )
    (comp (ref "R39")
      (value "47k")
      (footprint "easyedapro:R0603")
      (fields
        (field (name "Manufacturer Part") "0603WAF1001T5E")
        (field (name "Manufacturer") "UNI-ROYAL(厚声)")
      )
      (libsource (lib "easyedapro") (part "RES"))
    )
    (comp (ref "R40")
      (value "33R")
      (footprint "easyedapro:R0603")
      (fields
        (field (name "Manufacturer Part") "0603WAF1001T5E")
        (field (name "Manufacturer") "UNI-ROYAL(厚声)")
      )
      (libsource (lib "easyedapro") (part "RES"))
    )
    (comp (ref "R41")
      (value "33R")
      (footprint "easyedapro:R0603")
      (fields
        (field (name "Manufacturer Part") "0603WAF1001T5E")
        (field (name "Manufacturer") "UNI-ROYAL(厚声)")
      )
      (libsource (lib "easyedapro") (part "RES"))
    )
    (comp (ref "R42")
      (value "33R")
      (footprint "easyedapro:R0603")
      (fields
        (field (name "Manufacturer Part") "0603WAF1001T5E")
        (field (name "Manufacturer") "UNI-ROYAL(厚声)")
      )
      (libsource (lib "easyedapro") (part "RES"))
    )
    (comp (ref "R43")
      (value "100k")
      (footprint "easyedapro:R0603")
      (fields
        (field (name "Manufacturer Part") "0603WAF1001T5E")
        (field (name "Manufacturer") "UNI-ROYAL(厚声)")
      )
      (libsource (lib "easyedapro") (part "RES"))
    )
    (comp (ref "R44")
      (value "1M 1%")
      (footprint "easyedapro:R0603")
      (fields
        (field (name "Manufacturer Part") "0603WAF1001T5E")
        (field (name "Manufacturer") "UNI-ROYAL(厚声)")
      )
      (libsource (lib "easyedapro") (part "RES"))
    )
    (comp (ref "R45")
      (value "330k 1%")
      (footprint "easyedapro:R0603")
      (fields
        (field (name "Manufacturer Part") "0603WAF1001T5E")
        (field (name "Manufacturer") "UNI-ROYAL(厚声)")
      )
      (libsource (lib "easyedapro") (part "RES"))
    )
    (comp (ref "U7")
      (value "MAX98357AETE+T")
      (footprint "easyedapro:TQFN-16_L3.0-W3.0-P0.50-BL-EP1.5")
      (libsource (lib "easyedapro") (part "RURI_MAX98357"))
    )
    (comp (ref "C1")
      (value "10uF / 10V X5R")
      (footprint "easyedapro:C0603")
      (libsource (lib "easyedapro") (part "CAP"))
    )
    (comp (ref "C2")
      (value "100nF / 10V X7R")
      (footprint "easyedapro:C0603")
      (libsource (lib "easyedapro") (part "CAP"))
    )
    (comp (ref "C3")
      (value "1uF")
      (footprint "easyedapro:C0603")
      (fields
        (field (name "Manufacturer Part") "CL10A105KB8NNNC")
        (field (name "Manufacturer") "SAMSUNG(三星)")
        (field (name "Tolerance") "±10%")
      )
      (libsource (lib "easyedapro") (part "CAP"))
    )
    (comp (ref "C4")
      (value "DNP / tune after signal test")
      (footprint "easyedapro:C0603")
      (libsource (lib "easyedapro") (part "CAP"))
    )
    (comp (ref "C5")
      (value "DNP / tune after signal test")
      (footprint "easyedapro:C0603")
      (libsource (lib "easyedapro") (part "CAP"))
    )
    (comp (ref "R1")
      (value "10kΩ")
      (footprint "easyedapro:R0603")
      (fields
        (field (name "Manufacturer Part") "0603WAF1002T5E")
        (field (name "Manufacturer") "UNI-ROYAL(厚声)")
        (field (name "Tolerance") "±1%")
      )
      (libsource (lib "easyedapro") (part "RES"))
    )
    (comp (ref "R2")
      (value "22R / 1%")
      (footprint "easyedapro:R0603")
      (fields
        (field (name "Manufacturer Part") "0603WAF1001T5E")
        (field (name "Manufacturer") "UNI-ROYAL(厚声)")
      )
      (libsource (lib "easyedapro") (part "RES"))
    )
    (comp (ref "R3")
      (value "22R / 1%")
      (footprint "easyedapro:R0603")
      (fields
        (field (name "Manufacturer Part") "0603WAF1001T5E")
        (field (name "Manufacturer") "UNI-ROYAL(厚声)")
      )
      (libsource (lib "easyedapro") (part "RES"))
    )
    (comp (ref "U1")
      (value "2.4GHz")
      (footprint "easyedapro:WIRELM-SMD_ESP32-S3-WROOM-1")
      (fields
        (field (name "Manufacturer Part") "ESP32-S3-WROOM-1-N16R8")
        (field (name "Manufacturer") "ESPRESSIF(乐鑫)")
        (field (name "Utilized IC / Part") "ESP32-S3R8")
      )
      (libsource (lib "easyedapro") (part "RURI_ESP32_S3_WROOM1"))
    )
    (comp (ref "C6")
      (value "100nF / 10V X7R")
      (footprint "easyedapro:C0603")
      (libsource (lib "easyedapro") (part "CAP"))
    )
    (comp (ref "C7")
      (value "4.7uF / 10V X5R")
      (footprint "easyedapro:C0603")
      (libsource (lib "easyedapro") (part "CAP"))
    )
    (comp (ref "J1")
      (value "FH12A-40S-0.5SH(55)")
      (footprint "easyedapro:RURI_FH12A40_TOP_DRAFT")
      (fields (field (name "Manufacturer") "HRS(广濑)"))
      (libsource (lib "easyedapro") (part "RURI_LCD_CL40_40PIN"))
    )
    (comp (ref "R4")
      (value "10kΩ")
      (footprint "easyedapro:R0603")
      (fields
        (field (name "Manufacturer Part") "0603WAF1002T5E")
        (field (name "Manufacturer") "UNI-ROYAL(厚声)")
        (field (name "Tolerance") "±1%")
      )
      (libsource (lib "easyedapro") (part "RES"))
    )
    (comp (ref "R5")
      (value "10kΩ")
      (footprint "easyedapro:R0603")
      (fields
        (field (name "Manufacturer Part") "0603WAF1002T5E")
        (field (name "Manufacturer") "UNI-ROYAL(厚声)")
        (field (name "Tolerance") "±1%")
      )
      (libsource (lib "easyedapro") (part "RES"))
    )
    (comp (ref "C8")
      (value "100nF / 10V X7R")
      (footprint "easyedapro:C0603")
      (libsource (lib "easyedapro") (part "CAP"))
    )
    (comp (ref "R6")
      (value "4.7k")
      (footprint "easyedapro:R0603")
      (fields
        (field (name "Manufacturer Part") "0603WAF1001T5E")
        (field (name "Manufacturer") "UNI-ROYAL(厚声)")
      )
      (libsource (lib "easyedapro") (part "RES"))
    )
    (comp (ref "R7")
      (value "4.7k")
      (footprint "easyedapro:R0603")
      (fields
        (field (name "Manufacturer Part") "0603WAF1001T5E")
        (field (name "Manufacturer") "UNI-ROYAL(厚声)")
      )
      (libsource (lib "easyedapro") (part "RES"))
    )
    (comp (ref "R8")
      (value "10kΩ")
      (footprint "easyedapro:R0603")
      (fields
        (field (name "Manufacturer Part") "0603WAF1002T5E")
        (field (name "Manufacturer") "UNI-ROYAL(厚声)")
        (field (name "Tolerance") "±1%")
      )
      (libsource (lib "easyedapro") (part "RES"))
    )
    (comp (ref "R9")
      (value "100k")
      (footprint "easyedapro:R0603")
      (fields
        (field (name "Manufacturer Part") "0603WAF1001T5E")
        (field (name "Manufacturer") "UNI-ROYAL(厚声)")
      )
      (libsource (lib "easyedapro") (part "RES"))
    )
    (comp (ref "R10")
      (value "100k")
      (footprint "easyedapro:R0603")
      (fields
        (field (name "Manufacturer Part") "0603WAF1001T5E")
        (field (name "Manufacturer") "UNI-ROYAL(厚声)")
      )
      (libsource (lib "easyedapro") (part "RES"))
    )
    (comp (ref "R11")
      (value "100k")
      (footprint "easyedapro:R0603")
      (fields
        (field (name "Manufacturer Part") "0603WAF1001T5E")
        (field (name "Manufacturer") "UNI-ROYAL(厚声)")
      )
      (libsource (lib "easyedapro") (part "RES"))
    )
    (comp (ref "R12")
      (value "100k")
      (footprint "easyedapro:R0603")
      (fields
        (field (name "Manufacturer Part") "0603WAF1001T5E")
        (field (name "Manufacturer") "UNI-ROYAL(厚声)")
      )
      (libsource (lib "easyedapro") (part "RES"))
    )
    (comp (ref "R13")
      (value "100k")
      (footprint "easyedapro:R0603")
      (fields
        (field (name "Manufacturer Part") "0603WAF1001T5E")
        (field (name "Manufacturer") "UNI-ROYAL(厚声)")
      )
      (libsource (lib "easyedapro") (part "RES"))
    )
    (comp (ref "R14")
      (value "100k")
      (footprint "easyedapro:R0603")
      (fields
        (field (name "Manufacturer Part") "0603WAF1001T5E")
        (field (name "Manufacturer") "UNI-ROYAL(厚声)")
      )
      (libsource (lib "easyedapro") (part "RES"))
    )
    (comp (ref "R15")
      (value "10kΩ")
      (footprint "easyedapro:R0603")
      (fields
        (field (name "Manufacturer Part") "0603WAF1002T5E")
        (field (name "Manufacturer") "UNI-ROYAL(厚声)")
        (field (name "Tolerance") "±1%")
      )
      (libsource (lib "easyedapro") (part "RES"))
    )
    (comp (ref "R16")
      (value "10kΩ")
      (footprint "easyedapro:R0603")
      (fields
        (field (name "Manufacturer Part") "0603WAF1002T5E")
        (field (name "Manufacturer") "UNI-ROYAL(厚声)")
        (field (name "Tolerance") "±1%")
      )
      (libsource (lib "easyedapro") (part "RES"))
    )
    (comp (ref "R17")
      (value "10kΩ")
      (footprint "easyedapro:R0603")
      (fields
        (field (name "Manufacturer Part") "0603WAF1002T5E")
        (field (name "Manufacturer") "UNI-ROYAL(厚声)")
        (field (name "Tolerance") "±1%")
      )
      (libsource (lib "easyedapro") (part "RES"))
    )
    (comp (ref "R18")
      (value "10kΩ")
      (footprint "easyedapro:R0603")
      (fields
        (field (name "Manufacturer Part") "0603WAF1002T5E")
        (field (name "Manufacturer") "UNI-ROYAL(厚声)")
        (field (name "Tolerance") "±1%")
      )
      (libsource (lib "easyedapro") (part "RES"))
    )
    (comp (ref "R19")
      (value "10kΩ")
      (footprint "easyedapro:R0603")
      (fields
        (field (name "Manufacturer Part") "0603WAF1002T5E")
        (field (name "Manufacturer") "UNI-ROYAL(厚声)")
        (field (name "Tolerance") "±1%")
      )
      (libsource (lib "easyedapro") (part "RES"))
    )
    (comp (ref "R30")
      (value "100kΩ")
      (footprint "easyedapro:R0603")
      (fields
        (field (name "Manufacturer Part") "0603WAF1003T5E")
        (field (name "Manufacturer") "UNI-ROYAL(厚声)")
      )
      (libsource (lib "easyedapro") (part "0603WAF1003T5E"))
    )
    (comp (ref "R77")
      (value "10kΩ")
      (footprint "easyedapro:R0603")
      (fields
        (field (name "Manufacturer Part") "0603WAF1002T5E")
        (field (name "Manufacturer") "UNI-ROYAL(厚声)")
      )
      (libsource (lib "easyedapro") (part "0603WAF1002T5E"))
    )
    (comp (ref "R78")
      (value "10kΩ")
      (footprint "easyedapro:R0603")
      (fields
        (field (name "Manufacturer Part") "0603WAF1002T5E")
        (field (name "Manufacturer") "UNI-ROYAL(厚声)")
      )
      (libsource (lib "easyedapro") (part "0603WAF1002T5E"))
    )
    (comp (ref "R79")
      (value "10kΩ")
      (footprint "easyedapro:R0603")
      (fields
        (field (name "Manufacturer Part") "0603WAF1002T5E")
        (field (name "Manufacturer") "UNI-ROYAL(厚声)")
      )
      (libsource (lib "easyedapro") (part "0603WAF1002T5E"))
    )
    (comp (ref "R80")
      (value "10kΩ")
      (footprint "easyedapro:R0603")
      (fields
        (field (name "Manufacturer Part") "0603WAF1002T5E")
        (field (name "Manufacturer") "UNI-ROYAL(厚声)")
      )
      (libsource (lib "easyedapro") (part "0603WAF1002T5E"))
    )
    (comp (ref "R81")
      (value "10kΩ")
      (footprint "easyedapro:R0603")
      (fields
        (field (name "Manufacturer Part") "0603WAF1002T5E")
        (field (name "Manufacturer") "UNI-ROYAL(厚声)")
      )
      (libsource (lib "easyedapro") (part "0603WAF1002T5E"))
    )
    (comp (ref "R82")
      (value "10kΩ")
      (footprint "easyedapro:R0603")
      (fields
        (field (name "Manufacturer Part") "0603WAF1002T5E")
        (field (name "Manufacturer") "UNI-ROYAL(厚声)")
      )
      (libsource (lib "easyedapro") (part "0603WAF1002T5E"))
    )
    (comp (ref "R83")
      (value "10kΩ")
      (footprint "easyedapro:R0603")
      (fields
        (field (name "Manufacturer Part") "0603WAF1002T5E")
        (field (name "Manufacturer") "UNI-ROYAL(厚声)")
      )
      (libsource (lib "easyedapro") (part "0603WAF1002T5E"))
    )
    (comp (ref "SW1")
      (value "TS-1187A-A-I-B")
      (footprint "easyedapro:SW-SMD_4P-L5.1-W5.1-P3.70-LS6.5-TL_H1.7")
      (fields (field (name "Manufacturer") "XKB Connection(中国星坤)"))
      (libsource (lib "easyedapro") (part "RURI_SW_NO"))
    )
    (comp (ref "SW2")
      (value "TS-1187A-A-I-B")
      (footprint "easyedapro:SW-SMD_4P-L5.1-W5.1-P3.70-LS6.5-TL_H1.7")
      (fields (field (name "Manufacturer") "XKB Connection(中国星坤)"))
      (libsource (lib "easyedapro") (part "RURI_SW_NO"))
    )
    (comp (ref "SW3")
      (value "TS-1187A-A-I-B")
      (footprint "easyedapro:SW-SMD_4P-L5.1-W5.1-P3.70-LS6.5-TL_H1.7")
      (fields (field (name "Manufacturer") "XKB Connection(中国星坤)"))
      (libsource (lib "easyedapro") (part "RURI_SW_NO"))
    )
    (comp (ref "SW4")
      (value "TS-1187A-A-I-B")
      (footprint "easyedapro:SW-SMD_4P-L5.1-W5.1-P3.70-LS6.5-TL_H1.7")
      (fields (field (name "Manufacturer") "XKB Connection(中国星坤)"))
      (libsource (lib "easyedapro") (part "RURI_SW_NO"))
    )
    (comp (ref "SW5")
      (value "TS-1187A-A-I-B")
      (footprint "easyedapro:SW-SMD_4P-L5.1-W5.1-P3.70-LS6.5-TL_H1.7")
      (fields (field (name "Manufacturer") "XKB Connection(中国星坤)"))
      (libsource (lib "easyedapro") (part "RURI_SW_NO"))
    )
    (comp (ref "U2")
      (value "XL9535")
      (footprint "easyedapro:TSSOP-24_L7.8-W4.4-P0.65-LS6.4-BL")
      (fields (field (name "Manufacturer") "XINLUDA(信路达)"))
      (libsource (lib "easyedapro") (part "RURI_TCA9535_PW"))
    )
    (comp (ref "C9")
      (value "1uF")
      (footprint "easyedapro:C0603")
      (fields
        (field (name "Manufacturer Part") "CL10A105KB8NNNC")
        (field (name "Manufacturer") "SAMSUNG(三星)")
        (field (name "Tolerance") "±10%")
      )
      (libsource (lib "easyedapro") (part "CAP"))
    )
    (comp (ref "C10")
      (value "10uF / 10V X5R")
      (footprint "easyedapro:C0603")
      (libsource (lib "easyedapro") (part "CAP"))
    )
    (comp (ref "C11")
      (value "10uF / 10V X5R")
      (footprint "easyedapro:C0603")
      (libsource (lib "easyedapro") (part "CAP"))
    )
    (comp (ref "C12")
      (value "10uF / 10V X5R")
      (footprint "easyedapro:C0603")
      (libsource (lib "easyedapro") (part "CAP"))
    )
    (comp (ref "C13")
      (value "22uF / 10V X5R")
      (footprint "easyedapro:C0603")
      (libsource (lib "easyedapro") (part "CAP"))
    )
    (comp (ref "C14")
      (value "22uF / 10V X5R")
      (footprint "easyedapro:C0603")
      (libsource (lib "easyedapro") (part "CAP"))
    )
    (comp (ref "C15")
      (value "1uF")
      (footprint "easyedapro:C0603")
      (fields
        (field (name "Manufacturer Part") "CL10A105KB8NNNC")
        (field (name "Manufacturer") "SAMSUNG(三星)")
        (field (name "Tolerance") "±10%")
      )
      (libsource (lib "easyedapro") (part "CAP"))
    )
    (comp (ref "C16")
      (value "1uF")
      (footprint "easyedapro:C0603")
      (fields
        (field (name "Manufacturer Part") "CL10A105KB8NNNC")
        (field (name "Manufacturer") "SAMSUNG(三星)")
        (field (name "Tolerance") "±10%")
      )
      (libsource (lib "easyedapro") (part "CAP"))
    )
    (comp (ref "C60")
      (value "100nF")
      (footprint "easyedapro:C0603")
      (fields
        (field (name "Manufacturer Part") "CC0603KRX7R9BB104")
        (field (name "Manufacturer") "YAGEO(国巨)")
      )
      (libsource (lib "easyedapro") (part "CC0603KRX7R9BB104"))
    )
    (comp (ref "C61")
      (value "100nF")
      (footprint "easyedapro:C0603")
      (fields
        (field (name "Manufacturer Part") "CC0603KRX7R9BB104")
        (field (name "Manufacturer") "YAGEO(国巨)")
      )
      (libsource (lib "easyedapro") (part "CC0603KRX7R9BB104"))
    )
    (comp (ref "C62")
      (value "1uF")
      (footprint "easyedapro:C0603")
      (fields
        (field (name "Manufacturer Part") "CL10A105KB8NNNC")
        (field (name "Manufacturer") "SAMSUNG(三星)")
        (field (name "Tolerance") "±10%")
      )
      (libsource (lib "easyedapro") (part "CL10A105KB8NNNC"))
    )
    (comp (ref "C63")
      (value "100nF")
      (footprint "easyedapro:C0603")
      (fields
        (field (name "Manufacturer Part") "CC0603KRX7R9BB104")
        (field (name "Manufacturer") "YAGEO(国巨)")
      )
      (libsource (lib "easyedapro") (part "CC0603KRX7R9BB104"))
    )
    (comp (ref "J2")
      (value "USB4105-GF-A")
      (footprint "easyedapro:RURI_GCT_USB4105_REVB1")
      (libsource (lib "easyedapro") (part "RURI_USB4105"))
    )
    (comp (ref "J3")
      (value "S3B-XH-SM4-TB(LF)(SN)")
      (footprint "easyedapro:CONN-SMD_B3B-PH-SM4-TB-LF-SN")
      (fields (field (name "Manufacturer") "JST"))
      (libsource (lib "easyedapro") (part "RURI_BAT_PH3"))
    )
    (comp (ref "L1")
      (value "XFL4015-471MEC / 0.47uH")
      (footprint "easyedapro:IND-SMD_L4.0-W4.0_XFL4020-102MEB")
      (libsource (lib "easyedapro") (part "RURI_INDUCTOR"))
    )
    (comp (ref "Q11")
      (value "2N7002")
      (footprint "easyedapro:SOT-23-3_L2.9-W1.3-P1.90-LS2.4-BR")
      (fields (field (name "Manufacturer") "CJ(江苏长电/长晶)"))
      (libsource (lib "easyedapro") (part "2N7002"))
    )
    (comp (ref "Q12")
      (value "AO3401A")
      (footprint "easyedapro:SOT-23_L2.9-W1.3-P1.90-LS2.4-BR")
      (fields (field (name "Manufacturer") "AOS"))
      (libsource (lib "easyedapro") (part "AO3401A"))
    )
    (comp (ref "Q13")
      (value "AO3401A")
      (footprint "easyedapro:SOT-23_L2.9-W1.3-P1.90-LS2.4-BR")
      (fields (field (name "Manufacturer") "AOS"))
      (libsource (lib "easyedapro") (part "AO3401A"))
    )
    (comp (ref "Q14")
      (value "AO3401A")
      (footprint "easyedapro:SOT-23_L2.9-W1.3-P1.90-LS2.4-BR")
      (fields (field (name "Manufacturer") "AOS"))
      (libsource (lib "easyedapro") (part "AO3401A"))
    )
    (comp (ref "Q15")
      (value "2N7002")
      (footprint "easyedapro:SOT-23-3_L2.9-W1.3-P1.90-LS2.4-BR")
      (fields (field (name "Manufacturer") "CJ(江苏长电/长晶)"))
      (libsource (lib "easyedapro") (part "2N7002"))
    )
    (comp (ref "R20")
      (value "5.1k 1%")
      (footprint "easyedapro:R0603")
      (fields
        (field (name "Manufacturer Part") "0603WAF1001T5E")
        (field (name "Manufacturer") "UNI-ROYAL(厚声)")
      )
      (libsource (lib "easyedapro") (part "RES"))
    )
    (comp (ref "R21")
      (value "5.1k 1%")
      (footprint "easyedapro:R0603")
      (fields
        (field (name "Manufacturer Part") "0603WAF1001T5E")
        (field (name "Manufacturer") "UNI-ROYAL(厚声)")
      )
      (libsource (lib "easyedapro") (part "RES"))
    )
    (comp (ref "R22")
      (value "2.2kΩ")
      (footprint "easyedapro:R0603")
      (fields
        (field (name "Manufacturer Part") "0603WAF2201T5E")
        (field (name "Manufacturer") "UNI-ROYAL(厚声)")
        (field (name "Tolerance") "±1%")
      )
      (libsource (lib "easyedapro") (part "RES"))
    )
    (comp (ref "R23")
      (value "4.7kΩ")
      (footprint "easyedapro:R0603")
      (fields
        (field (name "Manufacturer Part") "0603WAF4701T5E")
        (field (name "Manufacturer") "UNI-ROYAL(厚声)")
        (field (name "Tolerance") "±1%")
      )
      (libsource (lib "easyedapro") (part "RES"))
    )
    (comp (ref "R24")
      (value "100k")
      (footprint "easyedapro:R0603")
      (fields
        (field (name "Manufacturer Part") "0603WAF1001T5E")
        (field (name "Manufacturer") "UNI-ROYAL(厚声)")
      )
      (libsource (lib "easyedapro") (part "RES"))
    )
    (comp (ref "R25")
      (value "100k")
      (footprint "easyedapro:R0603")
      (fields
        (field (name "Manufacturer Part") "0603WAF1001T5E")
        (field (name "Manufacturer") "UNI-ROYAL(厚声)")
      )
      (libsource (lib "easyedapro") (part "RES"))
    )
    (comp (ref "R26")
      (value "53.6k 0.1%")
      (footprint "easyedapro:R0603")
      (fields
        (field (name "Manufacturer Part") "0603WAF1001T5E")
        (field (name "Manufacturer") "UNI-ROYAL(厚声)")
      )
      (libsource (lib "easyedapro") (part "RES"))
    )
    (comp (ref "R27")
      (value "10k 0.1%")
      (footprint "easyedapro:R0603")
      (fields
        (field (name "Manufacturer Part") "0603WAF1001T5E")
        (field (name "Manufacturer") "UNI-ROYAL(厚声)")
      )
      (libsource (lib "easyedapro") (part "RES"))
    )
    (comp (ref "R28")
      (value "100k")
      (footprint "easyedapro:R0603")
      (fields
        (field (name "Manufacturer Part") "0603WAF1001T5E")
        (field (name "Manufacturer") "UNI-ROYAL(厚声)")
      )
      (libsource (lib "easyedapro") (part "RES"))
    )
    (comp (ref "R29")
      (value "100R")
      (footprint "easyedapro:R0603")
      (fields
        (field (name "Manufacturer Part") "0603WAF1001T5E")
        (field (name "Manufacturer") "UNI-ROYAL(厚声)")
      )
      (libsource (lib "easyedapro") (part "RES"))
    )
    (comp (ref "R31")
      (value "100k")
      (footprint "easyedapro:R0603")
      (fields
        (field (name "Manufacturer Part") "0603WAF1001T5E")
        (field (name "Manufacturer") "UNI-ROYAL(厚声)")
      )
      (libsource (lib "easyedapro") (part "RES"))
    )
    (comp (ref "R70")
      (value "100kΩ")
      (footprint "easyedapro:R0603")
      (fields
        (field (name "Manufacturer Part") "0603WAF1003T5E")
        (field (name "Manufacturer") "UNI-ROYAL(厚声)")
      )
      (libsource (lib "easyedapro") (part "0603WAF1003T5E"))
    )
    (comp (ref "R72")
      (value "100kΩ")
      (footprint "easyedapro:R0603")
      (fields
        (field (name "Manufacturer Part") "0603WAF1003T5E")
        (field (name "Manufacturer") "UNI-ROYAL(厚声)")
      )
      (libsource (lib "easyedapro") (part "0603WAF1003T5E"))
    )
    (comp (ref "R73")
      (value "10kΩ")
      (footprint "easyedapro:R0603")
      (fields
        (field (name "Manufacturer Part") "0603WAF1002T5E")
        (field (name "Manufacturer") "UNI-ROYAL(厚声)")
      )
      (libsource (lib "easyedapro") (part "0603WAF1002T5E"))
    )
    (comp (ref "R74")
      (value "100kΩ")
      (footprint "easyedapro:R0603")
      (fields
        (field (name "Manufacturer Part") "0603WAF1003T5E")
        (field (name "Manufacturer") "UNI-ROYAL(厚声)")
      )
      (libsource (lib "easyedapro") (part "0603WAF1003T5E"))
    )
    (comp (ref "R75")
      (value "100kΩ")
      (footprint "easyedapro:R0603")
      (fields
        (field (name "Manufacturer Part") "0603WAF1003T5E")
        (field (name "Manufacturer") "UNI-ROYAL(厚声)")
      )
      (libsource (lib "easyedapro") (part "0603WAF1003T5E"))
    )
    (comp (ref "R76")
      (value "100kΩ")
      (footprint "easyedapro:R0603")
      (fields
        (field (name "Manufacturer Part") "0603WAF1002T5E")
        (field (name "Manufacturer") "UNI-ROYAL(厚声)")
      )
      (libsource (lib "easyedapro") (part "0603WAF1002T5E"))
    )
    (comp (ref "SW6")
      (value "B3U-3000P / SIDE POWER")
      (footprint "easyedapro:KEY-SMD_B3U-3000P")
      (libsource (lib "easyedapro") (part "RURI_SIDE_SW"))
    )
    (comp (ref "U3")
      (value "BQ24074RGTR")
      (footprint "easyedapro:QFN-16_L3.0-W3.0-P0.50-TL-EP1.7")
      (libsource (lib "easyedapro") (part "RURI_BQ24074"))
    )
    (comp (ref "U4")
      (value "TPS63802DLAR")
      (footprint "easyedapro:VSON-HR-10_L3.0-W2.0-P0.50-TL")
      (libsource (lib "easyedapro") (part "RURI_TPS63802"))
    )
    (comp (ref "U5")
      (value "TPS22919DCKR")
      (footprint "easyedapro:SC-70-6_L2.2-W1.3-P0.65-LS2.1-BR")
      (libsource (lib "easyedapro") (part "RURI_TPS22919"))
    )
    (comp (ref "U10")
      (value "LTC2954CDDB-1#TRPBF")
      (footprint "easyedapro:DFN-8_L3.0-W2.0-P0.50-LS2.6-BL-EP")
      (fields (field (name "Manufacturer") "ADI(亚德诺)"))
      (libsource (lib "easyedapro") (part "LTC2954CDDB-1#TRPBF"))
    )
    (comp (ref "C29")
      (value "4.7uF / 10V X5R")
      (footprint "easyedapro:C0603")
      (libsource (lib "easyedapro") (part "CAP"))
    )
    (comp (ref "C30")
      (value "100nF / 10V X7R")
      (footprint "easyedapro:C0603")
      (libsource (lib "easyedapro") (part "CAP"))
    )
    (comp (ref "C31")
      (value "4.7uF / 10V X5R")
      (footprint "easyedapro:C0603")
      (libsource (lib "easyedapro") (part "CAP"))
    )
    (comp (ref "C32")
      (value "1uF / 10V X5R")
      (footprint "easyedapro:C0603")
      (libsource (lib "easyedapro") (part "CAP"))
    )
    (comp (ref "C33")
      (value "2.2uF / 10V X5R")
      (footprint "easyedapro:C0603")
      (libsource (lib "easyedapro") (part "CAP"))
    )
    (comp (ref "C34")
      (value "2.2uF / 10V X5R")
      (footprint "easyedapro:C0603")
      (libsource (lib "easyedapro") (part "CAP"))
    )
    (comp (ref "C35")
      (value "2.2uF / 10V X5R")
      (footprint "easyedapro:C0603")
      (libsource (lib "easyedapro") (part "CAP"))
    )
    (comp (ref "C36")
      (value "2.2uF / 10V X5R")
      (footprint "easyedapro:C0603")
      (libsource (lib "easyedapro") (part "CAP"))
    )
    (comp (ref "C37")
      (value "100nF / 10V X7R")
      (footprint "easyedapro:C0603")
      (libsource (lib "easyedapro") (part "CAP"))
    )
    (comp (ref "C38")
      (value "16pF / 50V C0G 2%")
      (footprint "easyedapro:C0603")
      (libsource (lib "easyedapro") (part "CAP"))
    )
    (comp (ref "C39")
      (value "16pF / 50V C0G 2%")
      (footprint "easyedapro:C0603")
      (libsource (lib "easyedapro") (part "CAP"))
    )
    (comp (ref "R59")
      (value "100k")
      (footprint "easyedapro:R0603")
      (fields
        (field (name "Manufacturer Part") "0603WAF1001T5E")
        (field (name "Manufacturer") "UNI-ROYAL(厚声)")
      )
      (libsource (lib "easyedapro") (part "RES"))
    )
    (comp (ref "U8")
      (value "PN7160A1HN/C100Y")
      (footprint "easyedapro:HVQFN-40_L6.0-W6.0-P0.50-BL-EP4.1")
      (libsource (lib "easyedapro") (part "RURI_PN7160"))
    )
    (comp (ref "Y1")
      (value "XRCGB27M120F3M10R0")
      (footprint "easyedapro:CRYSTAL-SMD_4P-L2.0-W1.6-BL")
      (libsource (lib "easyedapro") (part "RURI_XRCGB"))
    )
    (comp (ref "C24")
      (value "4.7uF / 10V X5R")
      (footprint "easyedapro:C0603")
      (libsource (lib "easyedapro") (part "CAP"))
    )
    (comp (ref "C25")
      (value "100nF / 10V X7R")
      (footprint "easyedapro:C0603")
      (libsource (lib "easyedapro") (part "CAP"))
    )
    (comp (ref "C26")
      (value "100nF / 10V X7R")
      (footprint "easyedapro:C0603")
      (libsource (lib "easyedapro") (part "CAP"))
    )
    (comp (ref "C27")
      (value "1uF / 10V X5R")
      (footprint "easyedapro:C0603")
      (libsource (lib "easyedapro") (part "CAP"))
    )
    (comp (ref "C28")
      (value "1nF")
      (footprint "easyedapro:C0603")
      (fields
        (field (name "Manufacturer Part") "CC0603FRNPO9BN102")
        (field (name "Manufacturer") "YAGEO(国巨)")
        (field (name "Tolerance") "±1%")
      )
      (libsource (lib "easyedapro") (part "CAP"))
    )
    (comp (ref "D4")
      (value "IR91-21C/TR10")
      (footprint "easyedapro:LED-SMD_IR91-21C-TR10")
      (libsource (lib "easyedapro") (part "RURI_IR91"))
    )
    (comp (ref "IR1")
      (value "IRM-H638T/TR2")
      (footprint "easyedapro:SENSOR-SMD_IRM-H638T-TR2-TL")
      (libsource (lib "easyedapro") (part "RURI_IRM_H638"))
    )
    (comp (ref "Q1")
      (value "AO3400A")
      (footprint "easyedapro:SOT-23-3_L2.9-W1.3-P1.90-LS2.4-BR")
      (libsource (lib "easyedapro") (part "RURI_AO3400A"))
    )
    (comp (ref "Q2")
      (value "AO3400A")
      (footprint "easyedapro:SOT-23-3_L2.9-W1.3-P1.90-LS2.4-BR")
      (libsource (lib "easyedapro") (part "RURI_AO3400A"))
    )
    (comp (ref "R46")
      (value "200R 1% >=0.125W")
      (footprint "easyedapro:R0603")
      (fields
        (field (name "Manufacturer Part") "0603WAF1001T5E")
        (field (name "Manufacturer") "UNI-ROYAL(厚声)")
      )
      (libsource (lib "easyedapro") (part "RES"))
    )
    (comp (ref "R47")
      (value "200R 1% >=0.125W")
      (footprint "easyedapro:R0603")
      (fields
        (field (name "Manufacturer Part") "0603WAF1001T5E")
        (field (name "Manufacturer") "UNI-ROYAL(厚声)")
      )
      (libsource (lib "easyedapro") (part "RES"))
    )
    (comp (ref "R48")
      (value "1kΩ")
      (footprint "easyedapro:R0603")
      (fields
        (field (name "Manufacturer Part") "0603WAF1001T5E")
        (field (name "Manufacturer") "UNI-ROYAL(厚声)")
        (field (name "Tolerance") "±1%")
      )
      (libsource (lib "easyedapro") (part "RES"))
    )
    (comp (ref "R49")
      (value "100k")
      (footprint "easyedapro:R0603")
      (fields
        (field (name "Manufacturer Part") "0603WAF1001T5E")
        (field (name "Manufacturer") "UNI-ROYAL(厚声)")
      )
      (libsource (lib "easyedapro") (part "RES"))
    )
    (comp (ref "R50")
      (value "47R")
      (footprint "easyedapro:R0603")
      (fields
        (field (name "Manufacturer Part") "0603WAF1001T5E")
        (field (name "Manufacturer") "UNI-ROYAL(厚声)")
      )
      (libsource (lib "easyedapro") (part "RES"))
    )
    (comp (ref "R51")
      (value "47k")
      (footprint "easyedapro:R0603")
      (fields
        (field (name "Manufacturer Part") "0603WAF1001T5E")
        (field (name "Manufacturer") "UNI-ROYAL(厚声)")
      )
      (libsource (lib "easyedapro") (part "RES"))
    )
    (comp (ref "R52")
      (value "20k 1%")
      (footprint "easyedapro:R0603")
      (fields
        (field (name "Manufacturer Part") "0603WAF1001T5E")
        (field (name "Manufacturer") "UNI-ROYAL(厚声)")
      )
      (libsource (lib "easyedapro") (part "RES"))
    )
    (comp (ref "R53")
      (value "1kΩ")
      (footprint "easyedapro:R0603")
      (fields
        (field (name "Manufacturer Part") "0603WAF1001T5E")
        (field (name "Manufacturer") "UNI-ROYAL(厚声)")
        (field (name "Tolerance") "±1%")
      )
      (libsource (lib "easyedapro") (part "RES"))
    )
    (comp (ref "R54")
      (value "1kΩ")
      (footprint "easyedapro:R0603")
      (fields
        (field (name "Manufacturer Part") "0603WAF1001T5E")
        (field (name "Manufacturer") "UNI-ROYAL(厚声)")
        (field (name "Tolerance") "±1%")
      )
      (libsource (lib "easyedapro") (part "RES"))
    )
    (comp (ref "R55")
      (value "100k")
      (footprint "easyedapro:R0603")
      (fields
        (field (name "Manufacturer Part") "0603WAF1001T5E")
        (field (name "Manufacturer") "UNI-ROYAL(厚声)")
      )
      (libsource (lib "easyedapro") (part "RES"))
    )
    (comp (ref "R56")
      (value "10kΩ")
      (footprint "easyedapro:R0603")
      (fields
        (field (name "Manufacturer Part") "0603WAF1002T5E")
        (field (name "Manufacturer") "UNI-ROYAL(厚声)")
        (field (name "Tolerance") "±1%")
      )
      (libsource (lib "easyedapro") (part "RES"))
    )
    (comp (ref "R57")
      (value "1R 1% >=0.1W")
      (footprint "easyedapro:R0603")
      (fields
        (field (name "Manufacturer Part") "0603WAF1001T5E")
        (field (name "Manufacturer") "UNI-ROYAL(厚声)")
      )
      (libsource (lib "easyedapro") (part "RES"))
    )
    (comp (ref "R58")
      (value "0R")
      (footprint "easyedapro:R0603")
      (fields
        (field (name "Manufacturer Part") "0603WAF1001T5E")
        (field (name "Manufacturer") "UNI-ROYAL(厚声)")
      )
      (libsource (lib "easyedapro") (part "RES"))
    )
    (comp (ref "U9")
      (value "TLV9001IDBVR")
      (footprint "easyedapro:SOT-23-5_L3.0-W1.7-P0.95-LS2.8-BR")
      (libsource (lib "easyedapro") (part "RURI_TLV9001"))
    )
    (comp (ref "ANT1")
      (value "PCB COIL / 34x24mm / 4T / TUNE")
      (footprint "easyedapro:RURI_NFC_COIL_34X24")
      (libsource (lib "easyedapro") (part "RURI_PCB_COIL"))
    )
    (comp (ref "C40")
      (value "750pF / 50V C0G 2%")
      (footprint "easyedapro:C0603")
      (libsource (lib "easyedapro") (part "CAP"))
    )
    (comp (ref "C41")
      (value "750pF / 50V C0G 2%")
      (footprint "easyedapro:C0603")
      (libsource (lib "easyedapro") (part "CAP"))
    )
    (comp (ref "C42")
      (value "62pF / 50V C0G 2%")
      (footprint "easyedapro:C0603")
      (libsource (lib "easyedapro") (part "CAP"))
    )
    (comp (ref "C43")
      (value "62pF / 50V C0G 2%")
      (footprint "easyedapro:C0603")
      (libsource (lib "easyedapro") (part "CAP"))
    )
    (comp (ref "C44")
      (value "200pF / 50V C0G 2%")
      (footprint "easyedapro:C0603")
      (libsource (lib "easyedapro") (part "CAP"))
    )
    (comp (ref "C45")
      (value "200pF / 50V C0G 2%")
      (footprint "easyedapro:C0603")
      (libsource (lib "easyedapro") (part "CAP"))
    )
    (comp (ref "C46")
      (value "1nF")
      (footprint "easyedapro:C0603")
      (fields
        (field (name "Manufacturer Part") "CC0603FRNPO9BN102")
        (field (name "Manufacturer") "YAGEO(国巨)")
        (field (name "Tolerance") "±1%")
      )
      (libsource (lib "easyedapro") (part "CAP"))
    )
    (comp (ref "C47")
      (value "1nF")
      (footprint "easyedapro:C0603")
      (fields
        (field (name "Manufacturer Part") "CC0603FRNPO9BN102")
        (field (name "Manufacturer") "YAGEO(国巨)")
        (field (name "Tolerance") "±1%")
      )
      (libsource (lib "easyedapro") (part "CAP"))
    )
    (comp (ref "C48")
      (value "DNP / TUNE C0G 50V")
      (footprint "easyedapro:C0603")
      (libsource (lib "easyedapro") (part "CAP"))
    )
    (comp (ref "C49")
      (value "DNP / TUNE C0G 50V")
      (footprint "easyedapro:C0603")
      (libsource (lib "easyedapro") (part "CAP"))
    )
    (comp (ref "C50")
      (value "DNP / TUNE C0G 50V")
      (footprint "easyedapro:C0603")
      (libsource (lib "easyedapro") (part "CAP"))
    )
    (comp (ref "C51")
      (value "DNP / TUNE C0G 50V")
      (footprint "easyedapro:C0603")
      (libsource (lib "easyedapro") (part "CAP"))
    )
    (comp (ref "D5")
      (value "TPD2EUSB30DRTR")
      (footprint "easyedapro:SOT-9X3-3_L1.0-W0.8-P0.35-LS1.0-BR")
      (libsource (lib "easyedapro") (part "RURI_TPD2EUSB30"))
    )
    (comp (ref "D6")
      (value "TPD2EUSB30DRTR")
      (footprint "easyedapro:SOT-9X3-3_L1.0-W0.8-P0.35-LS1.0-BR")
      (libsource (lib "easyedapro") (part "RURI_TPD2EUSB30"))
    )
    (comp (ref "D7")
      (value "TPD2EUSB30DRTR")
      (footprint "easyedapro:SOT-9X3-3_L1.0-W0.8-P0.35-LS1.0-BR")
      (libsource (lib "easyedapro") (part "RURI_TPD2EUSB30"))
    )
    (comp (ref "L2")
      (value "160nH LQW18CNR16J00D")
      (footprint "easyedapro:IND-SMD_L1.6-W0.8-1")
      (libsource (lib "easyedapro") (part "RURI_RF_L"))
    )
    (comp (ref "L3")
      (value "160nH LQW18CNR16J00D")
      (footprint "easyedapro:IND-SMD_L1.6-W0.8-1")
      (libsource (lib "easyedapro") (part "RURI_RF_L"))
    )
    (comp (ref "R60")
      (value "1R / 1% / 0.25W C17928")
      (footprint "easyedapro:R0603")
      (fields
        (field (name "Manufacturer Part") "0603WAF1001T5E")
        (field (name "Manufacturer") "UNI-ROYAL(厚声)")
      )
      (libsource (lib "easyedapro") (part "RES"))
    )
    (comp (ref "R61")
      (value "1R / 1% / 0.25W C17928")
      (footprint "easyedapro:R0603")
      (fields
        (field (name "Manufacturer Part") "0603WAF1001T5E")
        (field (name "Manufacturer") "UNI-ROYAL(厚声)")
      )
      (libsource (lib "easyedapro") (part "RES"))
    )
    (comp (ref "R62")
      (value "2.2k / 1%")
      (footprint "easyedapro:R0603")
      (fields
        (field (name "Manufacturer Part") "0603WAF1001T5E")
        (field (name "Manufacturer") "UNI-ROYAL(厚声)")
      )
      (libsource (lib "easyedapro") (part "RES"))
    )
    (comp (ref "R63")
      (value "2.2k / 1%")
      (footprint "easyedapro:R0603")
      (fields
        (field (name "Manufacturer Part") "0603WAF1001T5E")
        (field (name "Manufacturer") "UNI-ROYAL(厚声)")
      )
      (libsource (lib "easyedapro") (part "RES"))
    )
    (comp (ref "R64")
      (value "DNP / 6.8k / 1%")
      (footprint "easyedapro:R0603")
      (fields
        (field (name "Manufacturer Part") "0603WAF1001T5E")
        (field (name "Manufacturer") "UNI-ROYAL(厚声)")
      )
      (libsource (lib "easyedapro") (part "RES"))
    )
    (comp (ref "R65")
      (value "DNP / 6.8k / 1%")
      (footprint "easyedapro:R0603")
      (fields
        (field (name "Manufacturer Part") "0603WAF1001T5E")
        (field (name "Manufacturer") "UNI-ROYAL(厚声)")
      )
      (libsource (lib "easyedapro") (part "RES"))
    )
    (comp (ref "R66")
      (value "1R / 1% / 0.25W C17928")
      (footprint "easyedapro:R0603")
      (fields
        (field (name "Manufacturer Part") "0603WAF1001T5E")
        (field (name "Manufacturer") "UNI-ROYAL(厚声)")
      )
      (libsource (lib "easyedapro") (part "RES"))
    )
    (comp (ref "R67")
      (value "1R / 1% / 0.25W C17928")
      (footprint "easyedapro:R0603")
      (fields
        (field (name "Manufacturer Part") "0603WAF1001T5E")
        (field (name "Manufacturer") "UNI-ROYAL(厚声)")
      )
      (libsource (lib "easyedapro") (part "RES"))
    )
    (comp (ref "TP1")
      (value "BARE PAD / NO BOM")
      (footprint "easyedapro:RURI_TP_1MM")
      (libsource (lib "easyedapro") (part "RURI_TESTPAD"))
    )
    (comp (ref "TP2")
      (value "BARE PAD / NO BOM")
      (footprint "easyedapro:RURI_TP_1MM")
      (libsource (lib "easyedapro") (part "RURI_TESTPAD"))
    )
    (comp (ref "TP3")
      (value "BARE PAD / NO BOM")
      (footprint "easyedapro:RURI_TP_1MM")
      (libsource (lib "easyedapro") (part "RURI_TESTPAD"))
    )
    (comp (ref "TP4")
      (value "BARE PAD / NO BOM")
      (footprint "easyedapro:RURI_TP_1MM")
      (libsource (lib "easyedapro") (part "RURI_TESTPAD"))
    )
    (comp (ref "TP5")
      (value "BARE PAD / NO BOM")
      (footprint "easyedapro:RURI_TP_1MM")
      (libsource (lib "easyedapro") (part "RURI_TESTPAD"))
    )
    (comp (ref "TP6")
      (value "BARE PAD / NO BOM")
      (footprint "easyedapro:RURI_TP_1MM")
      (libsource (lib "easyedapro") (part "RURI_TESTPAD"))
    )
    (comp (ref "TP7")
      (value "BARE PAD / NO BOM")
      (footprint "easyedapro:RURI_TP_1MM")
      (libsource (lib "easyedapro") (part "RURI_TESTPAD"))
    )
    (comp (ref "TP8")
      (value "BARE PAD / NO BOM")
      (footprint "easyedapro:RURI_TP_1MM")
      (libsource (lib "easyedapro") (part "RURI_TESTPAD"))
    )
    (comp (ref "TP9")
      (value "BARE PAD / NO BOM")
      (footprint "easyedapro:RURI_TP_1MM")
      (libsource (lib "easyedapro") (part "RURI_TESTPAD"))
    )
    (comp (ref "TP10")
      (value "BARE PAD / NO BOM")
      (footprint "easyedapro:RURI_TP_1MM")
      (libsource (lib "easyedapro") (part "RURI_TESTPAD"))
    )
  )
  (nets
    (net (code "1") (name "3V18") (class "Default")
      (node (ref "C1") (pin "2") (pinfunction "2_2") (pintype "input"))
      (node (ref "C13") (pin "2") (pinfunction "2_2") (pintype "input"))
      (node (ref "C14") (pin "2") (pinfunction "2_2") (pintype "input"))
      (node (ref "C15") (pin "2") (pinfunction "2_2") (pintype "input"))
      (node (ref "C2") (pin "2") (pinfunction "2_2") (pintype "input"))
      (node (ref "C29") (pin "2") (pinfunction "2_2") (pintype "input"))
      (node (ref "C30") (pin "2") (pinfunction "2_2") (pintype "input"))
      (node (ref "C31") (pin "2") (pinfunction "2_2") (pintype "input"))
      (node (ref "C32") (pin "2") (pinfunction "2_2") (pintype "input"))
      (node (ref "C8") (pin "2") (pinfunction "2_2") (pintype "input"))
      (node (ref "R1") (pin "2") (pinfunction "2_2") (pintype "input"))
      (node (ref "R15") (pin "2") (pinfunction "2_2") (pintype "input"))
      (node (ref "R16") (pin "2") (pinfunction "2_2") (pintype "input"))
      (node (ref "R17") (pin "2") (pinfunction "2_2") (pintype "input"))
      (node (ref "R18") (pin "2") (pinfunction "2_2") (pintype "input"))
      (node (ref "R19") (pin "2") (pinfunction "2_2") (pintype "input"))
      (node (ref "R24") (pin "2") (pinfunction "2_2") (pintype "input"))
      (node (ref "R25") (pin "2") (pinfunction "2_2") (pintype "input"))
      (node (ref "R26") (pin "2") (pinfunction "2_2") (pintype "input"))
      (node (ref "R28") (pin "2") (pinfunction "2_2") (pintype "input"))
      (node (ref "R31") (pin "2") (pinfunction "2_2") (pintype "input"))
      (node (ref "R39") (pin "2") (pinfunction "2_2") (pintype "input"))
      (node (ref "R6") (pin "2") (pinfunction "2_2") (pintype "input"))
      (node (ref "R7") (pin "2") (pinfunction "2_2") (pintype "input"))
      (node (ref "R70") (pin "1") (pinfunction "1_1") (pintype "input"))
      (node (ref "R8") (pin "2") (pinfunction "2_2") (pintype "input"))
      (node (ref "TP2") (pin "1") (pinfunction "PAD_1") (pintype "unspecified"))
      (node (ref "U1") (pin "2") (pinfunction "3V18_2") (pintype "unspecified"))
      (node (ref "U2") (pin "24") (pinfunction "VCC_24") (pintype "unspecified"))
      (node (ref "U4") (pin "6") (pinfunction "VOUT_6") (pintype "unspecified"))
      (node (ref "U5") (pin "1") (pinfunction "VIN_1") (pintype "unspecified"))
      (node (ref "U8") (pin "12") (pinfunction "VBAT2_12") (pintype "unspecified"))
      (node (ref "U8") (pin "13") (pinfunction "VDD_UP_13") (pintype "unspecified"))
      (node (ref "U8") (pin "28") (pinfunction "VBAT_28") (pintype "unspecified"))
      (node (ref "U8") (pin "6") (pinfunction "VDD_PAD_6") (pintype "unspecified"))
    )
    (net (code "2") (name "3V18_PERIPH") (class "Default")
      (node (ref "C16") (pin "2") (pinfunction "2_2") (pintype "input"))
      (node (ref "C18") (pin "2") (pinfunction "2_2") (pintype "input"))
      (node (ref "C19") (pin "2") (pinfunction "2_2") (pintype "input"))
      (node (ref "C20") (pin "2") (pinfunction "2_2") (pintype "input"))
      (node (ref "C21") (pin "2") (pinfunction "2_2") (pintype "input"))
      (node (ref "C22") (pin "2") (pinfunction "2_2") (pintype "input"))
      (node (ref "C26") (pin "2") (pinfunction "2_2") (pintype "input"))
      (node (ref "C6") (pin "2") (pinfunction "2_2") (pintype "input"))
      (node (ref "C7") (pin "2") (pinfunction "2_2") (pintype "input"))
      (node (ref "J1") (pin "12") (pinfunction "RD_12") (pintype "unspecified"))
      (node (ref "J1") (pin "38") (pinfunction "IM0_38") (pintype "unspecified"))
      (node (ref "J1") (pin "39") (pinfunction "IM1_39") (pintype "unspecified"))
      (node (ref "J1") (pin "40") (pinfunction "IM2_40") (pintype "unspecified"))
      (node (ref "J1") (pin "6") (pinfunction "IOVCC_6") (pintype "unspecified"))
      (node (ref "J1") (pin "7") (pinfunction "VCC_7") (pintype "unspecified"))
      (node (ref "J4") (pin "4") (pinfunction "VDD_4") (pintype "unspecified"))
      (node (ref "MIC1") (pin "5") (pinfunction "VDD_5") (pintype "unspecified"))
      (node (ref "R29") (pin "2") (pinfunction "2_2") (pintype "input"))
      (node (ref "R34") (pin "2") (pinfunction "2_2") (pintype "input"))
      (node (ref "R35") (pin "2") (pinfunction "2_2") (pintype "input"))
      (node (ref "R36") (pin "2") (pinfunction "2_2") (pintype "input"))
      (node (ref "R37") (pin "2") (pinfunction "2_2") (pintype "input"))
      (node (ref "R38") (pin "2") (pinfunction "2_2") (pintype "input"))
      (node (ref "R4") (pin "2") (pinfunction "2_2") (pintype "input"))
      (node (ref "R50") (pin "1") (pinfunction "1_1") (pintype "input"))
      (node (ref "TP8") (pin "1") (pinfunction "PAD_1") (pintype "unspecified"))
      (node (ref "U5") (pin "6") (pinfunction "VOUT_6") (pintype "unspecified"))
      (node (ref "U7") (pin "7") (pinfunction "VDD_7") (pintype "unspecified"))
      (node (ref "U7") (pin "8") (pinfunction "VDD_8") (pintype "unspecified"))
      (node (ref "U9") (pin "5") (pinfunction "V+_5") (pintype "unspecified"))
    )
    (net (code "3") (name "AMP_ENABLE") (class "Default")
      (node (ref "R10") (pin "2") (pinfunction "2_2") (pintype "input"))
      (node (ref "U2") (pin "15") (pinfunction "P12_15") (pintype "unspecified"))
      (node (ref "U7") (pin "4") (pinfunction "SD_MODE_4") (pintype "unspecified"))
    )
    (net (code "4") (name "ANT_A") (class "Default")
      (node (ref "ANT1") (pin "1") (pinfunction "A_1") (pintype "unspecified"))
      (node (ref "R64") (pin "2") (pinfunction "2_2") (pintype "input"))
      (node (ref "R66") (pin "1") (pinfunction "1_1") (pintype "input"))
    )
    (net (code "5") (name "ANT_B") (class "Default")
      (node (ref "ANT1") (pin "2") (pinfunction "B_2") (pintype "unspecified"))
      (node (ref "R65") (pin "2") (pinfunction "2_2") (pintype "input"))
      (node (ref "R67") (pin "1") (pinfunction "1_1") (pintype "input"))
    )
    (net (code "6") (name "BAT_ADC_GATE") (class "Default")
      (node (ref "Q14") (pin "1") (pinfunction "G_1") (pintype "unspecified"))
      (node (ref "Q15") (pin "3") (pinfunction "D_3") (pintype "unspecified"))
      (node (ref "R75") (pin "2") (pinfunction "2_2") (pintype "input"))
    )
    (net (code "7") (name "BAT_NTC") (class "Default")
      (node (ref "J3") (pin "2") (pinfunction "NTC_2") (pintype "unspecified"))
      (node (ref "U3") (pin "1") (pinfunction "TS_1") (pintype "unspecified"))
    )
    (net (code "8") (name "BL_FB") (class "Default")
      (node (ref "C28") (pin "2") (pinfunction "2_2") (pintype "input"))
      (node (ref "R56") (pin "2") (pinfunction "2_2") (pintype "input"))
      (node (ref "U9") (pin "4") (pinfunction "IN-_4") (pintype "unspecified"))
    )
    (net (code "9") (name "BL_GATE") (class "Default")
      (node (ref "Q2") (pin "1") (pinfunction "G_1") (pintype "unspecified"))
      (node (ref "R54") (pin "2") (pinfunction "2_2") (pintype "input"))
      (node (ref "R55") (pin "2") (pinfunction "2_2") (pintype "input"))
    )
    (net (code "10") (name "BL_OP_OUT") (class "Default")
      (node (ref "C28") (pin "1") (pinfunction "1_1") (pintype "input"))
      (node (ref "R54") (pin "1") (pinfunction "1_1") (pintype "input"))
      (node (ref "U9") (pin "1") (pinfunction "OUT_1") (pintype "unspecified"))
    )
    (net (code "11") (name "BL_REF") (class "Default")
      (node (ref "C27") (pin "2") (pinfunction "2_2") (pintype "input"))
      (node (ref "R52") (pin "2") (pinfunction "2_2") (pintype "input"))
      (node (ref "R53") (pin "2") (pinfunction "2_2") (pintype "input"))
      (node (ref "U9") (pin "3") (pinfunction "IN+_3") (pintype "unspecified"))
    )
    (net (code "12") (name "BL_SENSE") (class "Default")
      (node (ref "Q2") (pin "2") (pinfunction "S_2") (pintype "unspecified"))
      (node (ref "R56") (pin "1") (pinfunction "1_1") (pintype "input"))
      (node (ref "R57") (pin "2") (pinfunction "2_2") (pintype "input"))
    )
    (net (code "13") (name "BOOT_N") (class "Default")
      (node (ref "TP4") (pin "1") (pinfunction "PAD_1") (pintype "unspecified"))
      (node (ref "U1") (pin "27") (pinfunction "IO0_27") (pintype "unspecified"))
    )
    (net (code "14") (name "CHG_EN1") (class "Default")
      (node (ref "R11") (pin "2") (pinfunction "2_2") (pintype "input"))
      (node (ref "U2") (pin "17") (pinfunction "P14_17") (pintype "unspecified"))
      (node (ref "U3") (pin "6") (pinfunction "EN1_6") (pintype "unspecified"))
    )
    (net (code "15") (name "CHG_EN2") (class "Default")
      (node (ref "R12") (pin "2") (pinfunction "2_2") (pintype "input"))
      (node (ref "U2") (pin "18") (pinfunction "P15_18") (pintype "unspecified"))
      (node (ref "U3") (pin "5") (pinfunction "EN2_5") (pintype "unspecified"))
    )
    (net (code "16") (name "CHG_ILIM") (class "Default")
      (node (ref "R23") (pin "2") (pinfunction "2_2") (pintype "input"))
      (node (ref "U3") (pin "12") (pinfunction "ILIM_12") (pintype "unspecified"))
    )
    (net (code "17") (name "CHG_ISET") (class "Default")
      (node (ref "R22") (pin "2") (pinfunction "2_2") (pintype "input"))
      (node (ref "U3") (pin "16") (pinfunction "ISET_16") (pintype "unspecified"))
    )
    (net (code "18") (name "CHG_STATUS_N") (class "Default")
      (node (ref "R24") (pin "1") (pinfunction "1_1") (pintype "input"))
      (node (ref "U2") (pin "11") (pinfunction "P07_11") (pintype "unspecified"))
      (node (ref "U3") (pin "9") (pinfunction "CHG_N_9") (pintype "unspecified"))
    )
    (net (code "19") (name "ESP_EN") (class "Default")
      (node (ref "C3") (pin "2") (pinfunction "2_2") (pintype "input"))
      (node (ref "R1") (pin "1") (pinfunction "1_1") (pintype "input"))
      (node (ref "TP3") (pin "1") (pinfunction "PAD_1") (pintype "unspecified"))
      (node (ref "U1") (pin "3") (pinfunction "EN_3") (pintype "unspecified"))
    )
    (net (code "20") (name "GND") (class "Default")
      (node (ref "C1") (pin "1") (pinfunction "1_1") (pintype "input"))
      (node (ref "C10") (pin "1") (pinfunction "1_1") (pintype "input"))
      (node (ref "C11") (pin "1") (pinfunction "1_1") (pintype "input"))
      (node (ref "C12") (pin "1") (pinfunction "1_1") (pintype "input"))
      (node (ref "C13") (pin "1") (pinfunction "1_1") (pintype "input"))
      (node (ref "C14") (pin "1") (pinfunction "1_1") (pintype "input"))
      (node (ref "C15") (pin "1") (pinfunction "1_1") (pintype "input"))
      (node (ref "C16") (pin "1") (pinfunction "1_1") (pintype "input"))
      (node (ref "C18") (pin "1") (pinfunction "1_1") (pintype "input"))
      (node (ref "C19") (pin "1") (pinfunction "1_1") (pintype "input"))
      (node (ref "C2") (pin "1") (pinfunction "1_1") (pintype "input"))
      (node (ref "C20") (pin "1") (pinfunction "1_1") (pintype "input"))
      (node (ref "C21") (pin "1") (pinfunction "1_1") (pintype "input"))
      (node (ref "C22") (pin "1") (pinfunction "1_1") (pintype "input"))
      (node (ref "C23") (pin "1") (pinfunction "1_1") (pintype "input"))
      (node (ref "C24") (pin "1") (pinfunction "1_1") (pintype "input"))
      (node (ref "C25") (pin "1") (pinfunction "1_1") (pintype "input"))
      (node (ref "C26") (pin "1") (pinfunction "1_1") (pintype "input"))
      (node (ref "C27") (pin "1") (pinfunction "1_1") (pintype "input"))
      (node (ref "C29") (pin "1") (pinfunction "1_1") (pintype "input"))
      (node (ref "C3") (pin "1") (pinfunction "1_1") (pintype "input"))
      (node (ref "C30") (pin "1") (pinfunction "1_1") (pintype "input"))
      (node (ref "C31") (pin "1") (pinfunction "1_1") (pintype "input"))
      (node (ref "C32") (pin "1") (pinfunction "1_1") (pintype "input"))
      (node (ref "C33") (pin "1") (pinfunction "1_1") (pintype "input"))
      (node (ref "C34") (pin "1") (pinfunction "1_1") (pintype "input"))
      (node (ref "C35") (pin "1") (pinfunction "1_1") (pintype "input"))
      (node (ref "C36") (pin "1") (pinfunction "1_1") (pintype "input"))
      (node (ref "C37") (pin "1") (pinfunction "1_1") (pintype "input"))
      (node (ref "C38") (pin "1") (pinfunction "1_1") (pintype "input"))
      (node (ref "C39") (pin "1") (pinfunction "1_1") (pintype "input"))
      (node (ref "C4") (pin "1") (pinfunction "1_1") (pintype "input"))
      (node (ref "C40") (pin "1") (pinfunction "1_1") (pintype "input"))
      (node (ref "C41") (pin "1") (pinfunction "1_1") (pintype "input"))
      (node (ref "C44") (pin "1") (pinfunction "1_1") (pintype "input"))
      (node (ref "C45") (pin "1") (pinfunction "1_1") (pintype "input"))
      (node (ref "C5") (pin "1") (pinfunction "1_1") (pintype "input"))
      (node (ref "C50") (pin "1") (pinfunction "1_1") (pintype "input"))
      (node (ref "C51") (pin "1") (pinfunction "1_1") (pintype "input"))
      (node (ref "C6") (pin "1") (pinfunction "1_1") (pintype "input"))
      (node (ref "C60") (pin "2") (pinfunction "2_2") (pintype "unspecified"))
      (node (ref "C61") (pin "2") (pinfunction "2_2") (pintype "unspecified"))
      (node (ref "C62") (pin "2") (pinfunction "2_2") (pintype "unspecified"))
      (node (ref "C7") (pin "1") (pinfunction "1_1") (pintype "input"))
      (node (ref "C8") (pin "1") (pinfunction "1_1") (pintype "input"))
      (node (ref "C9") (pin "1") (pinfunction "1_1") (pintype "input"))
      (node (ref "D1") (pin "3") (pinfunction "GND_3") (pintype "unspecified"))
      (node (ref "D2") (pin "3") (pinfunction "GND_3") (pintype "unspecified"))
      (node (ref "D3") (pin "3") (pinfunction "GND_3") (pintype "unspecified"))
      (node (ref "D5") (pin "3") (pinfunction "GND_3") (pintype "unspecified"))
      (node (ref "D6") (pin "3") (pinfunction "GND_3") (pintype "unspecified"))
      (node (ref "D7") (pin "3") (pinfunction "GND_3") (pintype "unspecified"))
      (node (ref "IR1") (pin "1") (pinfunction "GND_1") (pintype "unspecified"))
      (node (ref "IR1") (pin "2") (pinfunction "GND_2") (pintype "unspecified"))
      (node (ref "J1") (pin "16") (pinfunction "GND_16") (pintype "unspecified"))
      (node (ref "J1") (pin "17") (pinfunction "DB0_17") (pintype "unspecified"))
      (node (ref "J1") (pin "18") (pinfunction "DB1_18") (pintype "unspecified"))
      (node (ref "J1") (pin "19") (pinfunction "DB2_19") (pintype "unspecified"))
      (node (ref "J1") (pin "20") (pinfunction "DB3_20") (pintype "unspecified"))
      (node (ref "J1") (pin "21") (pinfunction "DB4_21") (pintype "unspecified"))
      (node (ref "J1") (pin "22") (pinfunction "DB5_22") (pintype "unspecified"))
      (node (ref "J1") (pin "23") (pinfunction "DB6_23") (pintype "unspecified"))
      (node (ref "J1") (pin "24") (pinfunction "DB7_24") (pintype "unspecified"))
      (node (ref "J1") (pin "25") (pinfunction "DB8_25") (pintype "unspecified"))
      (node (ref "J1") (pin "26") (pinfunction "DB9_26") (pintype "unspecified"))
      (node (ref "J1") (pin "27") (pinfunction "DB10_27") (pintype "unspecified"))
      (node (ref "J1") (pin "28") (pinfunction "DB11_28") (pintype "unspecified"))
      (node (ref "J1") (pin "29") (pinfunction "DB12_29") (pintype "unspecified"))
      (node (ref "J1") (pin "30") (pinfunction "DB13_30") (pintype "unspecified"))
      (node (ref "J1") (pin "31") (pinfunction "DB14_31") (pintype "unspecified"))
      (node (ref "J1") (pin "32") (pinfunction "DB15_32") (pintype "unspecified"))
      (node (ref "J1") (pin "37") (pinfunction "GND_37") (pintype "unspecified"))
      (node (ref "J1") (pin "5") (pinfunction "GND_5") (pintype "unspecified"))
      (node (ref "J2") (pin "1") (pinfunction "SHIELD_1") (pintype "unspecified"))
      (node (ref "J2") (pin "2") (pinfunction "SHIELD_2") (pintype "unspecified"))
      (node (ref "J2") (pin "3") (pinfunction "SHIELD_3") (pintype "unspecified"))
      (node (ref "J2") (pin "4") (pinfunction "SHIELD_4") (pintype "unspecified"))
      (node (ref "J2") (pin "A1") (pinfunction "GND_A1") (pintype "unspecified"))
      (node (ref "J2") (pin "A12") (pinfunction "GND_A12") (pintype "unspecified"))
      (node (ref "J2") (pin "B1") (pinfunction "GND_B1") (pintype "unspecified"))
      (node (ref "J2") (pin "B12") (pinfunction "GND_B12") (pintype "unspecified"))
      (node (ref "J3") (pin "3") (pinfunction "BAT-_3") (pintype "unspecified"))
      (node (ref "J3") (pin "4") (pinfunction "MP_4") (pintype "unspecified"))
      (node (ref "J3") (pin "5") (pinfunction "MP_5") (pintype "unspecified"))
      (node (ref "J4") (pin "10") (pinfunction "SHIELD_10") (pintype "unspecified"))
      (node (ref "J4") (pin "11") (pinfunction "SW_A_11") (pintype "unspecified"))
      (node (ref "J4") (pin "12") (pinfunction "SHIELD_12") (pintype "unspecified"))
      (node (ref "J4") (pin "13") (pinfunction "SHIELD_13") (pintype "unspecified"))
      (node (ref "J4") (pin "14") (pinfunction "SHIELD_14") (pintype "unspecified"))
      (node (ref "J4") (pin "6") (pinfunction "VSS_6") (pintype "unspecified"))
      (node (ref "J5") (pin "3") (pinfunction "MP_3") (pintype "unspecified"))
      (node (ref "J5") (pin "4") (pinfunction "MP_4") (pintype "unspecified"))
      (node (ref "MIC1") (pin "2") (pinfunction "SELECT_2") (pintype "unspecified"))
      (node (ref "MIC1") (pin "3") (pinfunction "GND_3") (pintype "unspecified"))
      (node (ref "Q1") (pin "2") (pinfunction "S_2") (pintype "unspecified"))
      (node (ref "Q11") (pin "2") (pinfunction "S_2") (pintype "unspecified"))
      (node (ref "Q15") (pin "2") (pinfunction "S_2") (pintype "unspecified"))
      (node (ref "R10") (pin "1") (pinfunction "1_1") (pintype "input"))
      (node (ref "R11") (pin "1") (pinfunction "1_1") (pintype "input"))
      (node (ref "R12") (pin "1") (pinfunction "1_1") (pintype "input"))
      (node (ref "R13") (pin "1") (pinfunction "1_1") (pintype "input"))
      (node (ref "R14") (pin "1") (pinfunction "1_1") (pintype "input"))
      (node (ref "R20") (pin "1") (pinfunction "1_1") (pintype "input"))
      (node (ref "R21") (pin "1") (pinfunction "1_1") (pintype "input"))
      (node (ref "R22") (pin "1") (pinfunction "1_1") (pintype "input"))
      (node (ref "R23") (pin "1") (pinfunction "1_1") (pintype "input"))
      (node (ref "R27") (pin "1") (pinfunction "1_1") (pintype "input"))
      (node (ref "R30") (pin "2") (pinfunction "2_2") (pintype "input"))
      (node (ref "R43") (pin "1") (pinfunction "1_1") (pintype "input"))
      (node (ref "R45") (pin "1") (pinfunction "1_1") (pintype "input"))
      (node (ref "R49") (pin "1") (pinfunction "1_1") (pintype "input"))
      (node (ref "R5") (pin "1") (pinfunction "1_1") (pintype "input"))
      (node (ref "R53") (pin "1") (pinfunction "1_1") (pintype "input"))
      (node (ref "R55") (pin "1") (pinfunction "1_1") (pintype "input"))
      (node (ref "R57") (pin "1") (pinfunction "1_1") (pintype "input"))
      (node (ref "R59") (pin "1") (pinfunction "1_1") (pintype "input"))
      (node (ref "R76") (pin "2") (pinfunction "2_2") (pintype "input"))
      (node (ref "R77") (pin "2") (pinfunction "2_2") (pintype "input"))
      (node (ref "R78") (pin "2") (pinfunction "2_2") (pintype "input"))
      (node (ref "R79") (pin "2") (pinfunction "2_2") (pintype "input"))
      (node (ref "R80") (pin "2") (pinfunction "2_2") (pintype "input"))
      (node (ref "R81") (pin "2") (pinfunction "2_2") (pintype "input"))
      (node (ref "R82") (pin "2") (pinfunction "2_2") (pintype "input"))
      (node (ref "R83") (pin "2") (pinfunction "2_2") (pintype "input"))
      (node (ref "R9") (pin "1") (pinfunction "1_1") (pintype "input"))
      (node (ref "SW1") (pin "2") (pinfunction "B_2") (pintype "unspecified"))
      (node (ref "SW1") (pin "4") (pinfunction "4_4") (pintype "unspecified"))
      (node (ref "SW2") (pin "2") (pinfunction "B_2") (pintype "unspecified"))
      (node (ref "SW2") (pin "4") (pinfunction "4_4") (pintype "unspecified"))
      (node (ref "SW3") (pin "2") (pinfunction "B_2") (pintype "unspecified"))
      (node (ref "SW3") (pin "4") (pinfunction "4_4") (pintype "unspecified"))
      (node (ref "SW4") (pin "2") (pinfunction "B_2") (pintype "unspecified"))
      (node (ref "SW4") (pin "4") (pinfunction "4_4") (pintype "unspecified"))
      (node (ref "SW5") (pin "2") (pinfunction "B_2") (pintype "unspecified"))
      (node (ref "SW5") (pin "4") (pinfunction "4_4") (pintype "unspecified"))
      (node (ref "SW6") (pin "2") (pinfunction "B_2") (pintype "unspecified"))
      (node (ref "TP1") (pin "1") (pinfunction "PAD_1") (pintype "unspecified"))
      (node (ref "U1") (pin "1") (pinfunction "GND_1") (pintype "unspecified"))
      (node (ref "U1") (pin "40") (pinfunction "GND_40") (pintype "unspecified"))
      (node (ref "U1") (pin "41") (pinfunction "EPAD_41") (pintype "unspecified"))
      (node (ref "U10") (pin "1") (pinfunction "GND_1") (pintype "unspecified"))
      (node (ref "U10") (pin "9") (pinfunction "EP_9") (pintype "unspecified"))
      (node (ref "U2") (pin "12") (pinfunction "GND_12") (pintype "unspecified"))
      (node (ref "U2") (pin "2") (pinfunction "A1_2") (pintype "unspecified"))
      (node (ref "U2") (pin "21") (pinfunction "A0_21") (pintype "unspecified"))
      (node (ref "U2") (pin "3") (pinfunction "A2_3") (pintype "unspecified"))
      (node (ref "U3") (pin "17") (pinfunction "EP_17") (pintype "unspecified"))
      (node (ref "U3") (pin "4") (pinfunction "CE_N_4") (pintype "unspecified"))
      (node (ref "U3") (pin "8") (pinfunction "VSS_8") (pintype "unspecified"))
      (node (ref "U4") (pin "3") (pinfunction "AGND_3") (pintype "unspecified"))
      (node (ref "U4") (pin "8") (pinfunction "PGND_8") (pintype "unspecified"))
      (node (ref "U5") (pin "2") (pinfunction "GND_2") (pintype "unspecified"))
      (node (ref "U7") (pin "11") (pinfunction "GND_11") (pintype "unspecified"))
      (node (ref "U7") (pin "15") (pinfunction "GND_15") (pintype "unspecified"))
      (node (ref "U7") (pin "17") (pinfunction "EP_17") (pintype "unspecified"))
      (node (ref "U7") (pin "2") (pinfunction "GAIN_SLOT_2") (pintype "unspecified"))
      (node (ref "U7") (pin "3") (pinfunction "GND_3") (pintype "unspecified"))
      (node (ref "U8") (pin "1") (pinfunction "ADR0_1") (pintype "unspecified"))
      (node (ref "U8") (pin "20") (pinfunction "VSS_TX_20") (pintype "unspecified"))
      (node (ref "U8") (pin "3") (pinfunction "ADR1_3") (pintype "unspecified"))
      (node (ref "U8") (pin "39") (pinfunction "WKUP_REQ_39") (pintype "unspecified"))
      (node (ref "U8") (pin "4") (pinfunction "VSS_PAD_4") (pintype "unspecified"))
      (node (ref "U8") (pin "41") (pinfunction "EP_41") (pintype "unspecified"))
      (node (ref "U8") (pin "9") (pinfunction "VSS_A_9") (pintype "unspecified"))
      (node (ref "U9") (pin "2") (pinfunction "V-_2") (pintype "unspecified"))
    )
    (net (code "21") (name "I2C_SCL") (class "Default")
      (node (ref "R7") (pin "1") (pinfunction "1_1") (pintype "input"))
      (node (ref "U1") (pin "38") (pinfunction "IO2_38") (pintype "unspecified"))
      (node (ref "U2") (pin "22") (pinfunction "SCL_22") (pintype "unspecified"))
      (node (ref "U8") (pin "7") (pinfunction "SCL_7") (pintype "unspecified"))
    )
    (net (code "22") (name "I2C_SDA") (class "Default")
      (node (ref "R6") (pin "1") (pinfunction "1_1") (pintype "input"))
      (node (ref "U1") (pin "36") (pinfunction "RXD0_36") (pintype "unspecified"))
      (node (ref "U2") (pin "23") (pinfunction "SDA_23") (pintype "unspecified"))
      (node (ref "U8") (pin "5") (pinfunction "SDA_5") (pintype "unspecified"))
    )
    (net (code "23") (name "I2S_BCLK") (class "Default")
      (node (ref "R40") (pin "1") (pinfunction "1_1") (pintype "input"))
      (node (ref "U1") (pin "32") (pinfunction "IO39_32") (pintype "unspecified"))
    )
    (net (code "24") (name "I2S_BCLK_AUDIO") (class "Default")
      (node (ref "MIC1") (pin "4") (pinfunction "BCLK_4") (pintype "unspecified"))
      (node (ref "R40") (pin "2") (pinfunction "2_2") (pintype "input"))
      (node (ref "U7") (pin "16") (pinfunction "BCLK_16") (pintype "unspecified"))
    )
    (net (code "25") (name "I2S_DIN") (class "Default")
      (node (ref "MIC1") (pin "6") (pinfunction "DOUT_6") (pintype "unspecified"))
      (node (ref "R43") (pin "2") (pinfunction "2_2") (pintype "input"))
      (node (ref "U1") (pin "35") (pinfunction "IO42_35") (pintype "unspecified"))
    )
    (net (code "26") (name "I2S_DOUT") (class "Default")
      (node (ref "R42") (pin "1") (pinfunction "1_1") (pintype "input"))
      (node (ref "U1") (pin "34") (pinfunction "IO41_34") (pintype "unspecified"))
    )
    (net (code "27") (name "I2S_DOUT_AUDIO") (class "Default")
      (node (ref "R42") (pin "2") (pinfunction "2_2") (pintype "input"))
      (node (ref "U7") (pin "1") (pinfunction "DIN_1") (pintype "unspecified"))
    )
    (net (code "28") (name "I2S_WS") (class "Default")
      (node (ref "R41") (pin "1") (pinfunction "1_1") (pintype "input"))
      (node (ref "U1") (pin "33") (pinfunction "IO40_33") (pintype "unspecified"))
    )
    (net (code "29") (name "I2S_WS_AUDIO") (class "Default")
      (node (ref "MIC1") (pin "1") (pinfunction "WS_1") (pintype "unspecified"))
      (node (ref "R41") (pin "2") (pinfunction "2_2") (pintype "input"))
      (node (ref "U7") (pin "14") (pinfunction "LRCLK_14") (pintype "unspecified"))
    )
    (net (code "30") (name "IOX_IRQ_N") (class "Default")
      (node (ref "R8") (pin "1") (pinfunction "1_1") (pintype "input"))
      (node (ref "U2") (pin "1") (pinfunction "INT_N_1") (pintype "unspecified"))
    )
    (net (code "31") (name "IOX_UNUSED_P00") (class "Default")
      (node (ref "R77") (pin "1") (pinfunction "1_1") (pintype "input"))
      (node (ref "U2") (pin "4") (pinfunction "P00_4") (pintype "unspecified"))
    )
    (net (code "32") (name "IOX_UNUSED_P01") (class "Default")
      (node (ref "R78") (pin "1") (pinfunction "1_1") (pintype "input"))
      (node (ref "U2") (pin "5") (pinfunction "P01_5") (pintype "unspecified"))
    )
    (net (code "33") (name "IOX_UNUSED_P02") (class "Default")
      (node (ref "R79") (pin "1") (pinfunction "1_1") (pintype "input"))
      (node (ref "U2") (pin "6") (pinfunction "P02_6") (pintype "unspecified"))
    )
    (net (code "34") (name "IOX_UNUSED_P03") (class "Default")
      (node (ref "R80") (pin "1") (pinfunction "1_1") (pintype "input"))
      (node (ref "U2") (pin "7") (pinfunction "P03_7") (pintype "unspecified"))
    )
    (net (code "35") (name "IOX_UNUSED_P04") (class "Default")
      (node (ref "R81") (pin "1") (pinfunction "1_1") (pintype "input"))
      (node (ref "U2") (pin "8") (pinfunction "P04_8") (pintype "unspecified"))
    )
    (net (code "36") (name "IOX_UNUSED_P06") (class "Default")
      (node (ref "R30") (pin "1") (pinfunction "1_1") (pintype "input"))
      (node (ref "R82") (pin "1") (pinfunction "1_1") (pintype "input"))
      (node (ref "U2") (pin "10") (pinfunction "P06_10") (pintype "unspecified"))
    )
    (net (code "37") (name "IOX_UNUSED_P11") (class "Default")
      (node (ref "R83") (pin "1") (pinfunction "1_1") (pintype "input"))
      (node (ref "U2") (pin "14") (pinfunction "P11_14") (pintype "unspecified"))
    )
    (net (code "38") (name "IR_GATE") (class "Default")
      (node (ref "Q1") (pin "1") (pinfunction "G_1") (pintype "unspecified"))
      (node (ref "R48") (pin "2") (pinfunction "2_2") (pintype "input"))
      (node (ref "R49") (pin "2") (pinfunction "2_2") (pintype "input"))
    )
    (net (code "39") (name "IR_LEDA") (class "Default")
      (node (ref "D4") (pin "2") (pinfunction "A_2") (pintype "unspecified"))
      (node (ref "R46") (pin "2") (pinfunction "2_2") (pintype "input"))
      (node (ref "R47") (pin "2") (pinfunction "2_2") (pintype "input"))
    )
    (net (code "40") (name "IR_LEDK") (class "Default")
      (node (ref "D4") (pin "1") (pinfunction "K_1") (pintype "unspecified"))
      (node (ref "Q1") (pin "3") (pinfunction "D_3") (pintype "unspecified"))
    )
    (net (code "41") (name "IR_RX") (class "Default")
      (node (ref "IR1") (pin "3") (pinfunction "OUT_3") (pintype "unspecified"))
      (node (ref "R51") (pin "1") (pinfunction "1_1") (pintype "input"))
      (node (ref "U1") (pin "31") (pinfunction "IO38_31") (pintype "unspecified"))
    )
    (net (code "42") (name "IR_RX_VCC") (class "Default")
      (node (ref "C24") (pin "2") (pinfunction "2_2") (pintype "input"))
      (node (ref "C25") (pin "2") (pinfunction "2_2") (pintype "input"))
      (node (ref "IR1") (pin "4") (pinfunction "VCC_4") (pintype "unspecified"))
      (node (ref "R50") (pin "2") (pinfunction "2_2") (pintype "input"))
      (node (ref "R51") (pin "2") (pinfunction "2_2") (pintype "input"))
    )
    (net (code "43") (name "IR_TX") (class "Default")
      (node (ref "R48") (pin "1") (pinfunction "1_1") (pintype "input"))
      (node (ref "U1") (pin "25") (pinfunction "IO48_25") (pintype "unspecified"))
    )
    (net (code "44") (name "KEY_DOWN_N") (class "Default")
      (node (ref "R16") (pin "1") (pinfunction "1_1") (pintype "input"))
      (node (ref "SW2") (pin "1") (pinfunction "A_1") (pintype "unspecified"))
      (node (ref "SW2") (pin "3") (pinfunction "3_3") (pintype "unspecified"))
      (node (ref "U1") (pin "5") (pinfunction "IO5_5") (pintype "unspecified"))
    )
    (net (code "45") (name "KEY_LEFT_N") (class "Default")
      (node (ref "R17") (pin "1") (pinfunction "1_1") (pintype "input"))
      (node (ref "SW3") (pin "1") (pinfunction "A_1") (pintype "unspecified"))
      (node (ref "SW3") (pin "3") (pinfunction "3_3") (pintype "unspecified"))
      (node (ref "U1") (pin "6") (pinfunction "IO6_6") (pintype "unspecified"))
    )
    (net (code "46") (name "KEY_OK_N") (class "Default")
      (node (ref "R19") (pin "1") (pinfunction "1_1") (pintype "input"))
      (node (ref "SW5") (pin "1") (pinfunction "A_1") (pintype "unspecified"))
      (node (ref "SW5") (pin "3") (pinfunction "3_3") (pintype "unspecified"))
      (node (ref "U1") (pin "8") (pinfunction "IO15_8") (pintype "unspecified"))
    )
    (net (code "47") (name "KEY_RIGHT_N") (class "Default")
      (node (ref "R18") (pin "1") (pinfunction "1_1") (pintype "input"))
      (node (ref "SW4") (pin "1") (pinfunction "A_1") (pintype "unspecified"))
      (node (ref "SW4") (pin "3") (pinfunction "3_3") (pintype "unspecified"))
      (node (ref "U1") (pin "7") (pinfunction "IO7_7") (pintype "unspecified"))
    )
    (net (code "48") (name "KEY_UP_N") (class "Default")
      (node (ref "R15") (pin "1") (pinfunction "1_1") (pintype "input"))
      (node (ref "SW1") (pin "1") (pinfunction "A_1") (pintype "unspecified"))
      (node (ref "SW1") (pin "3") (pinfunction "3_3") (pintype "unspecified"))
      (node (ref "U1") (pin "4") (pinfunction "IO4_4") (pintype "unspecified"))
    )
    (net (code "49") (name "LCD_BL_PWM") (class "Default")
      (node (ref "R52") (pin "1") (pinfunction "1_1") (pintype "input"))
      (node (ref "U1") (pin "37") (pinfunction "TXD0_37") (pintype "unspecified"))
    )
    (net (code "50") (name "LCD_CS_N") (class "Default")
      (node (ref "J1") (pin "9") (pinfunction "CS_9") (pintype "unspecified"))
      (node (ref "R4") (pin "1") (pinfunction "1_1") (pintype "input"))
      (node (ref "U1") (pin "18") (pinfunction "IO10_18") (pintype "unspecified"))
    )
    (net (code "51") (name "LCD_DC") (class "Default")
      (node (ref "J1") (pin "10") (pinfunction "RS_10") (pintype "unspecified"))
      (node (ref "U1") (pin "17") (pinfunction "IO9_17") (pintype "unspecified"))
    )
    (net (code "52") (name "LCD_LEDA") (class "Default")
      (node (ref "J1") (pin "33") (pinfunction "LEDA_33") (pintype "unspecified"))
      (node (ref "R58") (pin "2") (pinfunction "2_2") (pintype "input"))
    )
    (net (code "53") (name "LCD_LEDK") (class "Default")
      (node (ref "J1") (pin "34") (pinfunction "LEDK_34") (pintype "unspecified"))
      (node (ref "J1") (pin "35") (pinfunction "LEDK_35") (pintype "unspecified"))
      (node (ref "J1") (pin "36") (pinfunction "LEDK_36") (pintype "unspecified"))
      (node (ref "Q2") (pin "3") (pinfunction "D_3") (pintype "unspecified"))
    )
    (net (code "54") (name "LCD_MOSI") (class "Default")
      (node (ref "J1") (pin "13") (pinfunction "SPI_SDA_13") (pintype "unspecified"))
      (node (ref "U1") (pin "9") (pinfunction "IO16_9") (pintype "unspecified"))
    )
    (net (code "55") (name "LCD_RESET_N") (class "Default")
      (node (ref "J1") (pin "15") (pinfunction "RESET_15") (pintype "unspecified"))
      (node (ref "R5") (pin "2") (pinfunction "2_2") (pintype "input"))
      (node (ref "U2") (pin "13") (pinfunction "P10_13") (pintype "unspecified"))
    )
    (net (code "56") (name "LCD_SCK") (class "Default")
      (node (ref "J1") (pin "11") (pinfunction "WR_11") (pintype "unspecified"))
      (node (ref "U1") (pin "12") (pinfunction "IO8_12") (pintype "unspecified"))
    )
    (net (code "57") (name "MAIN_GATE") (class "Default")
      (node (ref "C63") (pin "2") (pinfunction "2_2") (pintype "unspecified"))
      (node (ref "Q12") (pin "1") (pinfunction "G_1") (pintype "unspecified"))
      (node (ref "Q13") (pin "1") (pinfunction "G_1") (pintype "unspecified"))
      (node (ref "R73") (pin "1") (pinfunction "1_1") (pintype "input"))
      (node (ref "R74") (pin "2") (pinfunction "2_2") (pintype "input"))
    )
    (net (code "58") (name "MAIN_SWITCH_D") (class "Default")
      (node (ref "Q11") (pin "3") (pinfunction "D_3") (pintype "unspecified"))
      (node (ref "R73") (pin "2") (pinfunction "2_2") (pintype "input"))
    )
    (net (code "59") (name "NFC_DWL_REQ") (class "Default")
      (node (ref "R59") (pin "2") (pinfunction "2_2") (pintype "input"))
      (node (ref "TP5") (pin "1") (pinfunction "PAD_1") (pintype "unspecified"))
      (node (ref "U8") (pin "2") (pinfunction "DWL_REQ_2") (pintype "unspecified"))
    )
    (net (code "60") (name "NFC_IRQ") (class "Default")
      (node (ref "TP9") (pin "1") (pinfunction "PAD_1") (pintype "unspecified"))
      (node (ref "U1") (pin "24") (pinfunction "IO47_24") (pintype "unspecified"))
      (node (ref "U8") (pin "8") (pinfunction "IRQ_8") (pintype "unspecified"))
    )
    (net (code "61") (name "NFC_RXN") (class "Default")
      (node (ref "C46") (pin "1") (pinfunction "1_1") (pintype "input"))
      (node (ref "U8") (pin "15") (pinfunction "RXN_15") (pintype "unspecified"))
    )
    (net (code "62") (name "NFC_RXP") (class "Default")
      (node (ref "C47") (pin "1") (pinfunction "1_1") (pintype "input"))
      (node (ref "U8") (pin "16") (pinfunction "RXP_16") (pintype "unspecified"))
    )
    (net (code "63") (name "NFC_TVDD") (class "Default")
      (node (ref "C35") (pin "2") (pinfunction "2_2") (pintype "input"))
      (node (ref "C36") (pin "2") (pinfunction "2_2") (pintype "input"))
      (node (ref "TP10") (pin "1") (pinfunction "PAD_1") (pintype "unspecified"))
      (node (ref "U8") (pin "14") (pinfunction "VDD_TX_14") (pintype "unspecified"))
      (node (ref "U8") (pin "18") (pinfunction "TVDD_IN_18") (pintype "unspecified"))
      (node (ref "U8") (pin "22") (pinfunction "TVDD_IN2_22") (pintype "unspecified"))
    )
    (net (code "64") (name "NFC_TX1") (class "Default")
      (node (ref "L2") (pin "1") (pinfunction "IN_1") (pintype "unspecified"))
      (node (ref "U8") (pin "21") (pinfunction "TX1_21") (pintype "unspecified"))
    )
    (net (code "65") (name "NFC_TX2") (class "Default")
      (node (ref "L3") (pin "1") (pinfunction "IN_1") (pintype "unspecified"))
      (node (ref "U8") (pin "19") (pinfunction "TX2_19") (pintype "unspecified"))
    )
    (net (code "66") (name "NFC_VDD18") (class "Default")
      (node (ref "C33") (pin "2") (pinfunction "2_2") (pintype "input"))
      (node (ref "C34") (pin "2") (pinfunction "2_2") (pintype "input"))
      (node (ref "U8") (pin "26") (pinfunction "VDD_A_26") (pintype "unspecified"))
      (node (ref "U8") (pin "27") (pinfunction "VDD_27") (pintype "unspecified"))
      (node (ref "U8") (pin "31") (pinfunction "VDD_D_31") (pintype "unspecified"))
    )
    (net (code "67") (name "NFC_VEN") (class "Default")
      (node (ref "R9") (pin "2") (pinfunction "2_2") (pintype "input"))
      (node (ref "U1") (pin "10") (pinfunction "IO17_10") (pintype "unspecified"))
      (node (ref "U8") (pin "10") (pinfunction "VEN_10") (pintype "unspecified"))
    )
    (net (code "68") (name "NFC_VMID") (class "Default")
      (node (ref "C37") (pin "2") (pinfunction "2_2") (pintype "input"))
      (node (ref "U8") (pin "17") (pinfunction "VDD_VMID_17") (pintype "unspecified"))
    )
    (net (code "69") (name "NFC_XTAL1") (class "Default")
      (node (ref "C38") (pin "2") (pinfunction "2_2") (pintype "input"))
      (node (ref "U8") (pin "30") (pinfunction "XTAL1_30") (pintype "unspecified"))
      (node (ref "Y1") (pin "1") (pinfunction "XTAL_1") (pintype "unspecified"))
    )
    (net (code "70") (name "NFC_XTAL2") (class "Default")
      (node (ref "C39") (pin "2") (pinfunction "2_2") (pintype "input"))
      (node (ref "U8") (pin "29") (pinfunction "XTAL2_29") (pintype "unspecified"))
      (node (ref "Y1") (pin "3") (pinfunction "XTAL_3") (pintype "unspecified"))
    )
    (net (code "71") (name "PERIPH_ENABLE") (class "Default")
      (node (ref "R13") (pin "2") (pinfunction "2_2") (pintype "input"))
      (node (ref "U2") (pin "19") (pinfunction "P16_19") (pintype "unspecified"))
      (node (ref "U5") (pin "3") (pinfunction "ON_3") (pintype "unspecified"))
    )
    (net (code "72") (name "PERIPH_QOD") (class "Default")
      (node (ref "R29") (pin "1") (pinfunction "1_1") (pintype "input"))
      (node (ref "U5") (pin "5") (pinfunction "QOD_5") (pintype "unspecified"))
    )
    (net (code "73") (name "PWR_BUTTON_N") (class "Default")
      (node (ref "SW6") (pin "1") (pinfunction "A_1") (pintype "unspecified"))
      (node (ref "U10") (pin "3") (pinfunction "PB#_3") (pintype "unspecified"))
    )
    (net (code "74") (name "PWR_EN") (class "Default")
      (node (ref "Q11") (pin "1") (pinfunction "G_1") (pintype "unspecified"))
      (node (ref "Q15") (pin "1") (pinfunction "G_1") (pintype "unspecified"))
      (node (ref "R72") (pin "2") (pinfunction "2_2") (pintype "input"))
      (node (ref "U10") (pin "7") (pinfunction "EN/EN#_7") (pintype "unspecified"))
    )
    (net (code "75") (name "PWR_INT_N") (class "Default")
      (node (ref "R31") (pin "1") (pinfunction "1_1") (pintype "input"))
      (node (ref "U1") (pin "11") (pinfunction "IO18_11") (pintype "unspecified"))
      (node (ref "U10") (pin "8") (pinfunction "INT#_8") (pintype "unspecified"))
    )
    (net (code "76") (name "PWR_KILL_N") (class "Default")
      (node (ref "R70") (pin "2") (pinfunction "2_2") (pintype "input"))
      (node (ref "U1") (pin "23") (pinfunction "IO21_23") (pintype "unspecified"))
      (node (ref "U10") (pin "5") (pinfunction "KILL#_5") (pintype "unspecified"))
    )
    (net (code "77") (name "PWR_ONT") (class "Default")
      (node (ref "C61") (pin "1") (pinfunction "1_1") (pintype "unspecified"))
      (node (ref "U10") (pin "2") (pinfunction "ONT_2") (pintype "unspecified"))
    )
    (net (code "78") (name "PWR_PDT") (class "Default")
      (node (ref "C62") (pin "1") (pinfunction "1_1") (pintype "unspecified"))
      (node (ref "U10") (pin "6") (pinfunction "PDT_6") (pintype "unspecified"))
    )
    (net (code "79") (name "REG_PWM") (class "Default")
      (node (ref "R14") (pin "2") (pinfunction "2_2") (pintype "input"))
      (node (ref "U2") (pin "20") (pinfunction "P17_20") (pintype "unspecified"))
      (node (ref "U4") (pin "2") (pinfunction "MODE_2") (pintype "unspecified"))
    )
    (net (code "80") (name "RF_DAMP_A") (class "Default")
      (node (ref "R60") (pin "1") (pinfunction "1_1") (pintype "input"))
      (node (ref "R66") (pin "2") (pinfunction "2_2") (pintype "input"))
    )
    (net (code "81") (name "RF_DAMP_B") (class "Default")
      (node (ref "R61") (pin "1") (pinfunction "1_1") (pintype "input"))
      (node (ref "R67") (pin "2") (pinfunction "2_2") (pintype "input"))
    )
    (net (code "82") (name "RF_EMC_A") (class "Default")
      (node (ref "C40") (pin "2") (pinfunction "2_2") (pintype "input"))
      (node (ref "C42") (pin "2") (pinfunction "2_2") (pintype "input"))
      (node (ref "C48") (pin "2") (pinfunction "2_2") (pintype "input"))
      (node (ref "L2") (pin "2") (pinfunction "OUT_2") (pintype "unspecified"))
      (node (ref "R62") (pin "2") (pinfunction "2_2") (pintype "input"))
    )
    (net (code "83") (name "RF_EMC_B") (class "Default")
      (node (ref "C41") (pin "2") (pinfunction "2_2") (pintype "input"))
      (node (ref "C43") (pin "2") (pinfunction "2_2") (pintype "input"))
      (node (ref "C49") (pin "2") (pinfunction "2_2") (pintype "input"))
      (node (ref "L3") (pin "2") (pinfunction "OUT_2") (pintype "unspecified"))
      (node (ref "R63") (pin "2") (pinfunction "2_2") (pintype "input"))
    )
    (net (code "84") (name "RF_MATCH_A") (class "Default")
      (node (ref "C42") (pin "1") (pinfunction "1_1") (pintype "input"))
      (node (ref "C44") (pin "2") (pinfunction "2_2") (pintype "input"))
      (node (ref "C48") (pin "1") (pinfunction "1_1") (pintype "input"))
      (node (ref "C50") (pin "2") (pinfunction "2_2") (pintype "input"))
      (node (ref "R60") (pin "2") (pinfunction "2_2") (pintype "input"))
    )
    (net (code "85") (name "RF_MATCH_B") (class "Default")
      (node (ref "C43") (pin "1") (pinfunction "1_1") (pintype "input"))
      (node (ref "C45") (pin "2") (pinfunction "2_2") (pintype "input"))
      (node (ref "C49") (pin "1") (pinfunction "1_1") (pintype "input"))
      (node (ref "C51") (pin "2") (pinfunction "2_2") (pintype "input"))
      (node (ref "R61") (pin "2") (pinfunction "2_2") (pintype "input"))
    )
    (net (code "86") (name "RF_RX_A") (class "Default")
      (node (ref "C46") (pin "2") (pinfunction "2_2") (pintype "input"))
      (node (ref "R62") (pin "1") (pinfunction "1_1") (pintype "input"))
      (node (ref "R64") (pin "1") (pinfunction "1_1") (pintype "input"))
    )
    (net (code "87") (name "RF_RX_B") (class "Default")
      (node (ref "C47") (pin "2") (pinfunction "2_2") (pintype "input"))
      (node (ref "R63") (pin "1") (pinfunction "1_1") (pintype "input"))
      (node (ref "R65") (pin "1") (pinfunction "1_1") (pintype "input"))
    )
    (net (code "88") (name "SD_CS_N") (class "Default")
      (node (ref "D5") (pin "2") (pinfunction "IO2_2") (pintype "unspecified"))
      (node (ref "J4") (pin "2") (pinfunction "DAT3_CS_2") (pintype "unspecified"))
      (node (ref "R35") (pin "1") (pinfunction "1_1") (pintype "input"))
      (node (ref "U1") (pin "22") (pinfunction "IO14_22") (pintype "unspecified"))
    )
    (net (code "89") (name "SD_DAT1") (class "Default")
      (node (ref "D6") (pin "1") (pinfunction "IO1_1") (pintype "unspecified"))
      (node (ref "J4") (pin "8") (pinfunction "DAT1_8") (pintype "unspecified"))
      (node (ref "R38") (pin "1") (pinfunction "1_1") (pintype "input"))
    )
    (net (code "90") (name "SD_DAT2") (class "Default")
      (node (ref "D6") (pin "2") (pinfunction "IO2_2") (pintype "unspecified"))
      (node (ref "J4") (pin "1") (pinfunction "DAT2_1") (pintype "unspecified"))
      (node (ref "R34") (pin "1") (pinfunction "1_1") (pintype "input"))
    )
    (net (code "91") (name "SD_DETECT_N") (class "Default")
      (node (ref "J4") (pin "9") (pinfunction "SW_B_9") (pintype "unspecified"))
      (node (ref "R39") (pin "1") (pinfunction "1_1") (pintype "input"))
      (node (ref "U2") (pin "9") (pinfunction "P05_9") (pintype "unspecified"))
    )
    (net (code "92") (name "SD_MISO") (class "Default")
      (node (ref "D5") (pin "1") (pinfunction "IO1_1") (pintype "unspecified"))
      (node (ref "J4") (pin "7") (pinfunction "DAT0_MISO_7") (pintype "unspecified"))
      (node (ref "R37") (pin "1") (pinfunction "1_1") (pintype "input"))
      (node (ref "U1") (pin "21") (pinfunction "IO13_21") (pintype "unspecified"))
    )
    (net (code "93") (name "SD_MOSI") (class "Default")
      (node (ref "R32") (pin "1") (pinfunction "1_1") (pintype "input"))
      (node (ref "U1") (pin "19") (pinfunction "IO11_19") (pintype "unspecified"))
    )
    (net (code "94") (name "SD_MOSI_CARD") (class "Default")
      (node (ref "D3") (pin "2") (pinfunction "IO2_2") (pintype "unspecified"))
      (node (ref "J4") (pin "3") (pinfunction "CMD_MOSI_3") (pintype "unspecified"))
      (node (ref "R32") (pin "2") (pinfunction "2_2") (pintype "input"))
      (node (ref "R36") (pin "1") (pinfunction "1_1") (pintype "input"))
    )
    (net (code "95") (name "SD_SCK") (class "Default")
      (node (ref "R33") (pin "1") (pinfunction "1_1") (pintype "input"))
      (node (ref "U1") (pin "20") (pinfunction "IO12_20") (pintype "unspecified"))
    )
    (net (code "96") (name "SD_SCK_CARD") (class "Default")
      (node (ref "D3") (pin "1") (pinfunction "IO1_1") (pintype "unspecified"))
      (node (ref "J4") (pin "5") (pinfunction "CLK_5") (pintype "unspecified"))
      (node (ref "R33") (pin "2") (pinfunction "2_2") (pintype "input"))
    )
    (net (code "97") (name "SPK_OUT_N") (class "Default")
      (node (ref "J5") (pin "2") (pinfunction "SPK-_2") (pintype "unspecified"))
      (node (ref "U7") (pin "10") (pinfunction "OUTN_10") (pintype "unspecified"))
    )
    (net (code "98") (name "SPK_OUT_P") (class "Default")
      (node (ref "J5") (pin "1") (pinfunction "SPK+_1") (pintype "unspecified"))
      (node (ref "U7") (pin "9") (pinfunction "OUTP_9") (pintype "unspecified"))
    )
    (net (code "99") (name "USB_CC1") (class "Default")
      (node (ref "D2") (pin "1") (pinfunction "IO1_1") (pintype "unspecified"))
      (node (ref "J2") (pin "A5") (pinfunction "CC1_A5") (pintype "unspecified"))
      (node (ref "R20") (pin "2") (pinfunction "2_2") (pintype "input"))
    )
    (net (code "100") (name "USB_CC2") (class "Default")
      (node (ref "D2") (pin "2") (pinfunction "IO2_2") (pintype "unspecified"))
      (node (ref "J2") (pin "B5") (pinfunction "CC2_B5") (pintype "unspecified"))
      (node (ref "R21") (pin "2") (pinfunction "2_2") (pintype "input"))
    )
    (net (code "101") (name "USB_DM_CONN") (class "Default")
      (node (ref "D1") (pin "2") (pinfunction "IO2_2") (pintype "unspecified"))
      (node (ref "J2") (pin "A7") (pinfunction "D-_A7") (pintype "unspecified"))
      (node (ref "J2") (pin "B7") (pinfunction "D-_B7") (pintype "unspecified"))
      (node (ref "R2") (pin "2") (pinfunction "2_2") (pintype "input"))
    )
    (net (code "102") (name "USB_DM_MCU") (class "Default")
      (node (ref "C4") (pin "2") (pinfunction "2_2") (pintype "input"))
      (node (ref "R2") (pin "1") (pinfunction "1_1") (pintype "input"))
      (node (ref "U1") (pin "13") (pinfunction "IO19_13") (pintype "unspecified"))
    )
    (net (code "103") (name "USB_DP_CONN") (class "Default")
      (node (ref "D1") (pin "1") (pinfunction "IO1_1") (pintype "unspecified"))
      (node (ref "J2") (pin "A6") (pinfunction "D+_A6") (pintype "unspecified"))
      (node (ref "J2") (pin "B6") (pinfunction "D+_B6") (pintype "unspecified"))
      (node (ref "R3") (pin "2") (pinfunction "2_2") (pintype "input"))
    )
    (net (code "104") (name "USB_DP_MCU") (class "Default")
      (node (ref "C5") (pin "2") (pinfunction "2_2") (pintype "input"))
      (node (ref "R3") (pin "1") (pinfunction "1_1") (pintype "input"))
      (node (ref "U1") (pin "14") (pinfunction "IO20_14") (pintype "unspecified"))
    )
    (net (code "105") (name "USB_PGOOD_N") (class "Default")
      (node (ref "R25") (pin "1") (pinfunction "1_1") (pintype "input"))
      (node (ref "U2") (pin "16") (pinfunction "P13_16") (pintype "unspecified"))
      (node (ref "U3") (pin "7") (pinfunction "PGOOD_N_7") (pintype "unspecified"))
    )
    (net (code "106") (name "VBAT") (class "Default")
      (node (ref "C10") (pin "2") (pinfunction "2_2") (pintype "input"))
      (node (ref "J3") (pin "1") (pinfunction "BAT+_1") (pintype "unspecified"))
      (node (ref "Q14") (pin "2") (pinfunction "S_2") (pintype "unspecified"))
      (node (ref "R75") (pin "1") (pinfunction "1_1") (pintype "input"))
      (node (ref "TP7") (pin "1") (pinfunction "PAD_1") (pintype "unspecified"))
      (node (ref "U3") (pin "2") (pinfunction "BAT_2") (pintype "unspecified"))
      (node (ref "U3") (pin "3") (pinfunction "BAT_3") (pintype "unspecified"))
    )
    (net (code "107") (name "VBAT_ADC_SW") (class "Default")
      (node (ref "Q14") (pin "3") (pinfunction "D_3") (pintype "unspecified"))
      (node (ref "R44") (pin "2") (pinfunction "2_2") (pintype "input"))
    )
    (net (code "108") (name "VBAT_SENSE") (class "Default")
      (node (ref "C23") (pin "2") (pinfunction "2_2") (pintype "input"))
      (node (ref "R44") (pin "1") (pinfunction "1_1") (pintype "input"))
      (node (ref "R45") (pin "2") (pinfunction "2_2") (pintype "input"))
      (node (ref "U1") (pin "39") (pinfunction "IO1_39") (pintype "unspecified"))
    )
    (net (code "109") (name "VBUS_5V") (class "Default")
      (node (ref "C9") (pin "2") (pinfunction "2_2") (pintype "input"))
      (node (ref "D7") (pin "1") (pinfunction "IO1_1") (pintype "unspecified"))
      (node (ref "J2") (pin "A4") (pinfunction "VBUS_A4") (pintype "unspecified"))
      (node (ref "J2") (pin "A9") (pinfunction "VBUS_A9") (pintype "unspecified"))
      (node (ref "J2") (pin "B4") (pinfunction "VBUS_B4") (pintype "unspecified"))
      (node (ref "J2") (pin "B9") (pinfunction "VBUS_B9") (pintype "unspecified"))
      (node (ref "U3") (pin "13") (pinfunction "IN_13") (pintype "unspecified"))
    )
    (net (code "110") (name "VREG_FB") (class "Default")
      (node (ref "R26") (pin "1") (pinfunction "1_1") (pintype "input"))
      (node (ref "R27") (pin "2") (pinfunction "2_2") (pintype "input"))
      (node (ref "U4") (pin "4") (pinfunction "FB_4") (pintype "unspecified"))
    )
    (net (code "111") (name "VREG_L1") (class "Default")
      (node (ref "L1") (pin "1") (pinfunction "L1_1") (pintype "unspecified"))
      (node (ref "U4") (pin "9") (pinfunction "L1_9") (pintype "unspecified"))
    )
    (net (code "112") (name "VREG_L2") (class "Default")
      (node (ref "L1") (pin "2") (pinfunction "L2_2") (pintype "unspecified"))
      (node (ref "U4") (pin "7") (pinfunction "L2_7") (pintype "unspecified"))
    )
    (net (code "113") (name "VREG_PG") (class "Default")
      (node (ref "R28") (pin "1") (pinfunction "1_1") (pintype "input"))
      (node (ref "U4") (pin "5") (pinfunction "PG_5") (pintype "unspecified"))
    )
    (net (code "114") (name "VSYS") (class "Default")
      (node (ref "C11") (pin "2") (pinfunction "2_2") (pintype "input"))
      (node (ref "C60") (pin "1") (pinfunction "1_1") (pintype "unspecified"))
      (node (ref "C63") (pin "1") (pinfunction "1_1") (pintype "unspecified"))
      (node (ref "Q12") (pin "2") (pinfunction "S_2") (pintype "unspecified"))
      (node (ref "Q13") (pin "2") (pinfunction "S_2") (pintype "unspecified"))
      (node (ref "R72") (pin "1") (pinfunction "1_1") (pintype "input"))
      (node (ref "R74") (pin "1") (pinfunction "1_1") (pintype "input"))
      (node (ref "TP6") (pin "1") (pinfunction "PAD_1") (pintype "unspecified"))
      (node (ref "U10") (pin "4") (pinfunction "VIN_4") (pintype "unspecified"))
      (node (ref "U3") (pin "10") (pinfunction "OUT_10") (pintype "unspecified"))
      (node (ref "U3") (pin "11") (pinfunction "OUT_11") (pintype "unspecified"))
    )
    (net (code "115") (name "VSYS_RUN") (class "Default")
      (node (ref "C12") (pin "2") (pinfunction "2_2") (pintype "input"))
      (node (ref "Q12") (pin "3") (pinfunction "D_3") (pintype "unspecified"))
      (node (ref "Q13") (pin "3") (pinfunction "D_3") (pintype "unspecified"))
      (node (ref "R46") (pin "1") (pinfunction "1_1") (pintype "input"))
      (node (ref "R47") (pin "1") (pinfunction "1_1") (pintype "input"))
      (node (ref "R58") (pin "1") (pinfunction "1_1") (pintype "input"))
      (node (ref "R76") (pin "1") (pinfunction "1_1") (pintype "input"))
      (node (ref "U4") (pin "1") (pinfunction "EN_1") (pintype "unspecified"))
      (node (ref "U4") (pin "10") (pinfunction "VIN_10") (pintype "unspecified"))
    )
    (net (code "116") (name "unconnected-(D7-IO2-Pad2)") (class "Default")
      (node (ref "D7") (pin "2") (pinfunction "IO2_2") (pintype "unspecified+no_connect"))
    )
    (net (code "117") (name "unconnected-(J1-FMARK-Pad8)") (class "Default")
      (node (ref "J1") (pin "8") (pinfunction "FMARK_8") (pintype "unspecified+no_connect"))
    )
    (net (code "118") (name "unconnected-(J1-SPI_SDO-Pad14)") (class "Default")
      (node (ref "J1") (pin "14") (pinfunction "SPI_SDO_14") (pintype "unspecified+no_connect"))
    )
    (net (code "119") (name "unconnected-(J1-XL-Pad1)") (class "Default")
      (node (ref "J1") (pin "1") (pinfunction "XL_1") (pintype "unspecified+no_connect"))
    )
    (net (code "120") (name "unconnected-(J1-XR-Pad3)") (class "Default")
      (node (ref "J1") (pin "3") (pinfunction "XR_3") (pintype "unspecified+no_connect"))
    )
    (net (code "121") (name "unconnected-(J1-YD-Pad4)") (class "Default")
      (node (ref "J1") (pin "4") (pinfunction "YD_4") (pintype "unspecified+no_connect"))
    )
    (net (code "122") (name "unconnected-(J1-YU-Pad2)") (class "Default")
      (node (ref "J1") (pin "2") (pinfunction "YU_2") (pintype "unspecified+no_connect"))
    )
    (net (code "123") (name "unconnected-(J2-SBU1-PadA8)") (class "Default")
      (node (ref "J2") (pin "A8") (pinfunction "SBU1_A8") (pintype "unspecified+no_connect"))
    )
    (net (code "124") (name "unconnected-(J2-SBU2-PadB8)") (class "Default")
      (node (ref "J2") (pin "B8") (pinfunction "SBU2_B8") (pintype "unspecified+no_connect"))
    )
    (net (code "125") (name "unconnected-(U1-IO3-Pad15)") (class "Default")
      (node (ref "U1") (pin "15") (pinfunction "IO3_15") (pintype "unspecified+no_connect"))
    )
    (net (code "126") (name "unconnected-(U1-IO35-Pad28)") (class "Default")
      (node (ref "U1") (pin "28") (pinfunction "IO35_28") (pintype "unspecified+no_connect"))
    )
    (net (code "127") (name "unconnected-(U1-IO36-Pad29)") (class "Default")
      (node (ref "U1") (pin "29") (pinfunction "IO36_29") (pintype "unspecified+no_connect"))
    )
    (net (code "128") (name "unconnected-(U1-IO37-Pad30)") (class "Default")
      (node (ref "U1") (pin "30") (pinfunction "IO37_30") (pintype "unspecified+no_connect"))
    )
    (net (code "129") (name "unconnected-(U1-IO45-Pad26)") (class "Default")
      (node (ref "U1") (pin "26") (pinfunction "IO45_26") (pintype "unspecified+no_connect"))
    )
    (net (code "130") (name "unconnected-(U1-IO46-Pad16)") (class "Default")
      (node (ref "U1") (pin "16") (pinfunction "IO46_16") (pintype "unspecified+no_connect"))
    )
    (net (code "131") (name "unconnected-(U3-ITERM-Pad15)") (class "Default")
      (node (ref "U3") (pin "15") (pinfunction "ITERM_15") (pintype "unspecified+no_connect"))
    )
    (net (code "132") (name "unconnected-(U3-TMR-Pad14)") (class "Default")
      (node (ref "U3") (pin "14") (pinfunction "TMR_14") (pintype "unspecified+no_connect"))
    )
    (net (code "133") (name "unconnected-(U5-NC-Pad4)") (class "Default")
      (node (ref "U5") (pin "4") (pinfunction "NC_4") (pintype "unspecified+no_connect"))
    )
    (net (code "134") (name "unconnected-(U7-NC-Pad5)") (class "Default")
      (node (ref "U7") (pin "5") (pinfunction "NC_5") (pintype "unspecified+no_connect"))
    )
    (net (code "135") (name "unconnected-(U7-NC-Pad6)") (class "Default")
      (node (ref "U7") (pin "6") (pinfunction "NC_6") (pintype "unspecified+no_connect"))
    )
    (net (code "136") (name "unconnected-(U7-NC-Pad12)") (class "Default")
      (node (ref "U7") (pin "12") (pinfunction "NC_12") (pintype "unspecified+no_connect"))
    )
    (net (code "137") (name "unconnected-(U7-NC-Pad13)") (class "Default")
      (node (ref "U7") (pin "13") (pinfunction "NC_13") (pintype "unspecified+no_connect"))
    )
    (net (code "138") (name "unconnected-(U8-ANT1-Pad23)") (class "Default")
      (node (ref "U8") (pin "23") (pinfunction "ANT1_23") (pintype "unspecified+no_connect"))
    )
    (net (code "139") (name "unconnected-(U8-ANT2-Pad24)") (class "Default")
      (node (ref "U8") (pin "24") (pinfunction "ANT2_24") (pintype "unspecified+no_connect"))
    )
    (net (code "140") (name "unconnected-(U8-CLK_REQ-Pad40)") (class "Default")
      (node (ref "U8") (pin "40") (pinfunction "CLK_REQ_40") (pintype "unspecified+no_connect"))
    )
    (net (code "141") (name "unconnected-(U8-DCDC_EN-Pad37)") (class "Default")
      (node (ref "U8") (pin "37") (pinfunction "DCDC_EN_37") (pintype "unspecified+no_connect"))
    )
    (net (code "142") (name "unconnected-(U8-IC-Pad11)") (class "Default")
      (node (ref "U8") (pin "11") (pinfunction "IC_11") (pintype "unspecified+no_connect"))
    )
    (net (code "143") (name "unconnected-(U8-IC-Pad38)") (class "Default")
      (node (ref "U8") (pin "38") (pinfunction "IC_38") (pintype "unspecified+no_connect"))
    )
    (net (code "144") (name "unconnected-(U8-NC-Pad32)") (class "Default")
      (node (ref "U8") (pin "32") (pinfunction "NC_32") (pintype "unspecified+no_connect"))
    )
    (net (code "145") (name "unconnected-(U8-NC-Pad33)") (class "Default")
      (node (ref "U8") (pin "33") (pinfunction "NC_33") (pintype "unspecified+no_connect"))
    )
    (net (code "146") (name "unconnected-(U8-NC-Pad34)") (class "Default")
      (node (ref "U8") (pin "34") (pinfunction "NC_34") (pintype "unspecified+no_connect"))
    )
    (net (code "147") (name "unconnected-(U8-NC-Pad35)") (class "Default")
      (node (ref "U8") (pin "35") (pinfunction "NC_35") (pintype "unspecified+no_connect"))
    )
    (net (code "148") (name "unconnected-(U8-NC-Pad36)") (class "Default")
      (node (ref "U8") (pin "36") (pinfunction "NC_36") (pintype "unspecified+no_connect"))
    )
    (net (code "149") (name "unconnected-(U8-VDD_HF-Pad25)") (class "Default")
      (node (ref "U8") (pin "25") (pinfunction "VDD_HF_25") (pintype "unspecified+no_connect"))
    )
    (net (code "150") (name "unconnected-(Y1-NC-Pad2)") (class "Default")
      (node (ref "Y1") (pin "2") (pinfunction "NC_2") (pintype "unspecified+no_connect"))
    )
    (net (code "151") (name "unconnected-(Y1-NC-Pad4)") (class "Default")
      (node (ref "Y1") (pin "4") (pinfunction "NC_4") (pintype "unspecified+no_connect"))
    )
  )
)
